# combo-02.net
KiCad netlist of a schematic drawn in EAGLE
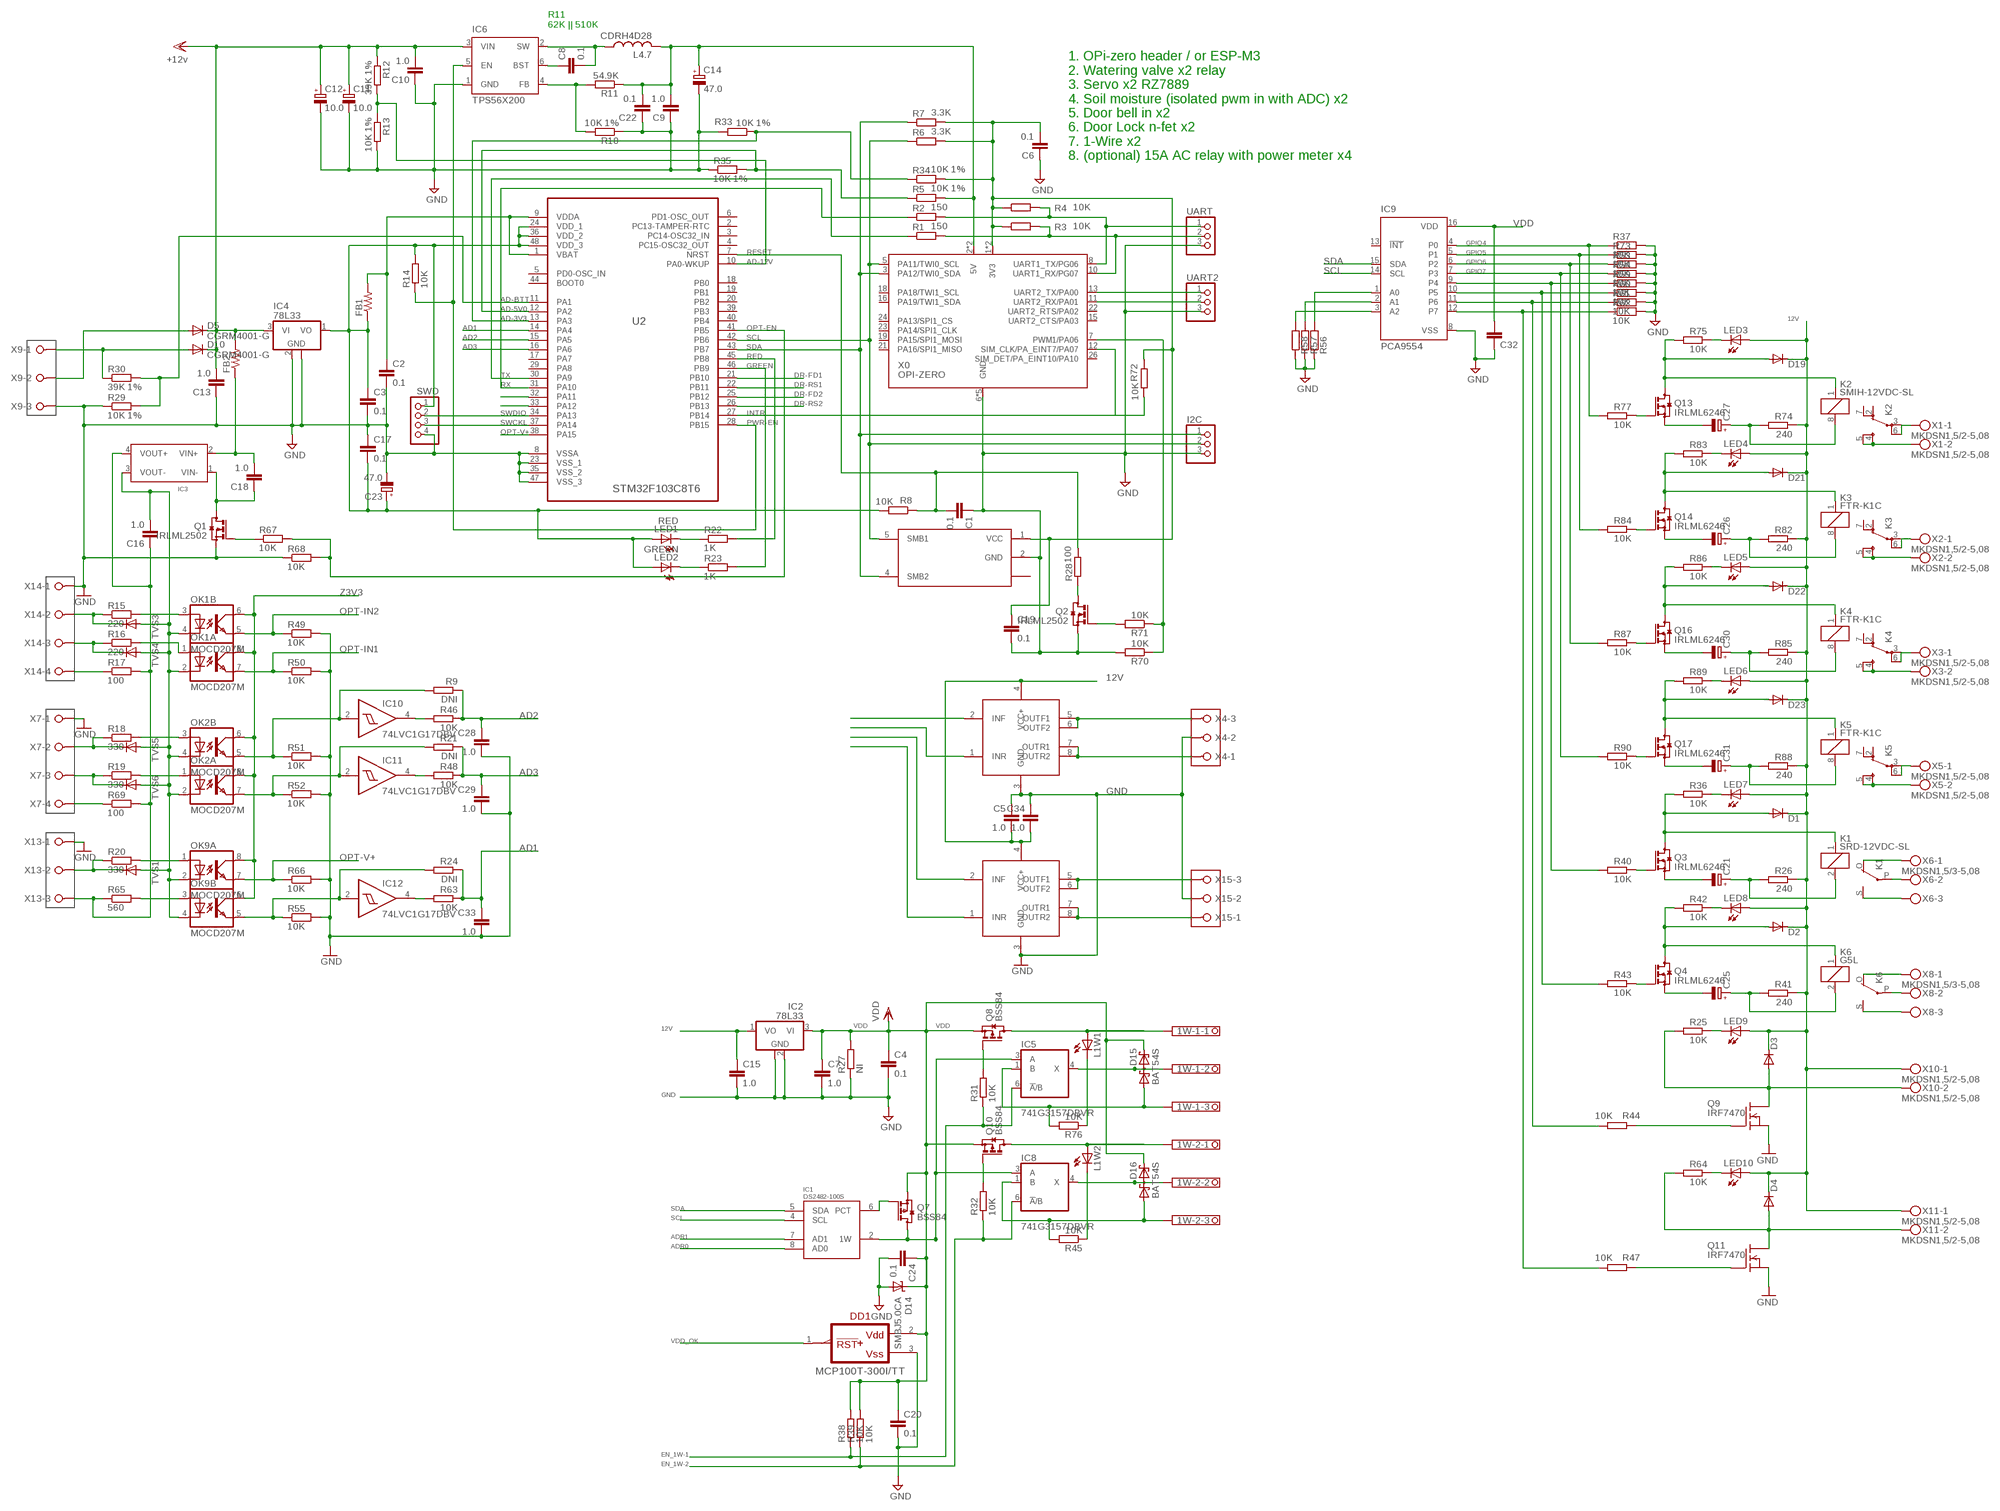
[diagram p0: schematic, sheet 1]

(export (version "E")
  (design (tool "Eeschema 10.0.6"))
  (components
    (comp (ref "1W-1")
      (value "1751251")
      (footprint "eagle-import:1751251")
      (libsource (lib "eagle-import") (part "1751251"))
    )
    (comp (ref "1W-2")
      (value "1751251")
      (footprint "eagle-import:1751251")
      (libsource (lib "eagle-import") (part "1751251"))
    )
    (comp (ref "C1")
      (value "0.1")
      (footprint "eagle-import:C0603")
      (libsource (lib "eagle-import") (part "C-EUC0603"))
    )
    (comp (ref "C2")
      (value "0.1")
      (footprint "eagle-import:C0603")
      (libsource (lib "eagle-import") (part "C-EUC0603"))
    )
    (comp (ref "C3")
      (value "0.1")
      (footprint "eagle-import:C0603")
      (libsource (lib "eagle-import") (part "C-EUC0603"))
    )
    (comp (ref "C4")
      (value "0.1")
      (footprint "eagle-import:C0603")
      (libsource (lib "eagle-import") (part "C-EUC0603"))
    )
    (comp (ref "C5")
      (value "1.0")
      (footprint "eagle-import:C0805")
      (libsource (lib "eagle-import") (part "C-EUC0805"))
    )
    (comp (ref "C6")
      (value "0.1")
      (footprint "eagle-import:C0805")
      (libsource (lib "eagle-import") (part "C-EUC0805"))
    )
    (comp (ref "C7")
      (value "1.0")
      (footprint "eagle-import:C0805")
      (libsource (lib "eagle-import") (part "C-EUC0805"))
    )
    (comp (ref "C8")
      (value "0.1")
      (footprint "eagle-import:C0805")
      (libsource (lib "eagle-import") (part "C-EUC0805"))
    )
    (comp (ref "C9")
      (value "1.0")
      (footprint "eagle-import:C0805")
      (libsource (lib "eagle-import") (part "C-EUC0805"))
    )
    (comp (ref "C10")
      (value "1.0")
      (footprint "eagle-import:C1206")
      (libsource (lib "eagle-import") (part "C-EUC1206"))
    )
    (comp (ref "C11")
      (value "10.0")
      (footprint "eagle-import:C_6032-28R")
      (libsource (lib "eagle-import") (part "CPOL-EUC/6032-28R"))
    )
    (comp (ref "C12")
      (value "10.0")
      (footprint "eagle-import:C_6032-28R")
      (libsource (lib "eagle-import") (part "CPOL-EUC/6032-28R"))
    )
    (comp (ref "C13")
      (value "1.0")
      (footprint "eagle-import:C1206")
      (libsource (lib "eagle-import") (part "C-EUC1206"))
    )
    (comp (ref "C14")
      (value "47.0")
      (footprint "eagle-import:B_3528-21R")
      (libsource (lib "eagle-import") (part "CPOL-EUB/3528-21R"))
    )
    (comp (ref "C15")
      (value "1.0")
      (footprint "eagle-import:C0805")
      (libsource (lib "eagle-import") (part "C-EUC0805"))
    )
    (comp (ref "C16")
      (value "1.0")
      (footprint "eagle-import:C1206")
      (libsource (lib "eagle-import") (part "C-EUC1206"))
    )
    (comp (ref "C17")
      (value "0.1")
      (footprint "eagle-import:C0603")
      (libsource (lib "eagle-import") (part "C-EUC0603"))
    )
    (comp (ref "C18")
      (value "1.0")
      (footprint "eagle-import:C1206")
      (libsource (lib "eagle-import") (part "C-EUC1206"))
    )
    (comp (ref "C19")
      (value "0.1")
      (footprint "eagle-import:C0603")
      (libsource (lib "eagle-import") (part "C-EUC0603"))
    )
    (comp (ref "C20")
      (value "0.1")
      (footprint "eagle-import:C0603")
      (libsource (lib "eagle-import") (part "C-EUC0603"))
    )
    (comp (ref "C21")
      (value "CPOL-EUE3.5-8")
      (footprint "eagle-import:E3,5-8")
      (libsource (lib "eagle-import") (part "CPOL-EUE3.5-8"))
    )
    (comp (ref "C22")
      (value "0.1")
      (footprint "eagle-import:C0805")
      (libsource (lib "eagle-import") (part "C-EUC0805"))
    )
    (comp (ref "C23")
      (value "47.0")
      (footprint "eagle-import:B_3528-21R")
      (libsource (lib "eagle-import") (part "CPOL-EUB/3528-21R"))
    )
    (comp (ref "C24")
      (value "0.1")
      (footprint "eagle-import:C0603")
      (libsource (lib "eagle-import") (part "C-EUC0603"))
    )
    (comp (ref "C25")
      (value "CPOL-EUE3.5-8")
      (footprint "eagle-import:E3,5-8")
      (libsource (lib "eagle-import") (part "CPOL-EUE3.5-8"))
    )
    (comp (ref "C26")
      (value "CPOL-EUE3.5-8")
      (footprint "eagle-import:E3,5-8")
      (libsource (lib "eagle-import") (part "CPOL-EUE3.5-8"))
    )
    (comp (ref "C27")
      (value "CPOL-EUE3.5-8")
      (footprint "eagle-import:E3,5-8")
      (libsource (lib "eagle-import") (part "CPOL-EUE3.5-8"))
    )
    (comp (ref "C28")
      (value "1.0")
      (footprint "eagle-import:C0805")
      (libsource (lib "eagle-import") (part "C-EUC0805"))
    )
    (comp (ref "C29")
      (value "1.0")
      (footprint "eagle-import:C0805")
      (libsource (lib "eagle-import") (part "C-EUC0805"))
    )
    (comp (ref "C30")
      (value "CPOL-EUE3.5-8")
      (footprint "eagle-import:E3,5-8")
      (libsource (lib "eagle-import") (part "CPOL-EUE3.5-8"))
    )
    (comp (ref "C31")
      (value "CPOL-EUE3.5-8")
      (footprint "eagle-import:E3,5-8")
      (libsource (lib "eagle-import") (part "CPOL-EUE3.5-8"))
    )
    (comp (ref "C32")
      (value "C-EUC0805")
      (footprint "eagle-import:C0805")
      (libsource (lib "eagle-import") (part "C-EUC0805"))
    )
    (comp (ref "C33")
      (value "1.0")
      (footprint "eagle-import:C0805")
      (libsource (lib "eagle-import") (part "C-EUC0805"))
    )
    (comp (ref "C34")
      (value "1.0")
      (footprint "eagle-import:C0805")
      (libsource (lib "eagle-import") (part "C-EUC0805"))
    )
    (comp (ref "D1")
      (value "DIODE-SOD123")
      (footprint "eagle-import:SOD123")
      (libsource (lib "eagle-import") (part "DIODE-SOD123"))
    )
    (comp (ref "D2")
      (value "DIODE-SOD123")
      (footprint "eagle-import:SOD123")
      (libsource (lib "eagle-import") (part "DIODE-SOD123"))
    )
    (comp (ref "D3")
      (value "DIODE-SOD123")
      (footprint "eagle-import:SOD123")
      (libsource (lib "eagle-import") (part "DIODE-SOD123"))
    )
    (comp (ref "D4")
      (value "DIODE-SOD123")
      (footprint "eagle-import:SOD123")
      (libsource (lib "eagle-import") (part "DIODE-SOD123"))
    )
    (comp (ref "D5")
      (value "CGRM4001-G")
      (footprint "eagle-import:SOD-123_MINI-SMA")
      (libsource (lib "eagle-import") (part "CGRM400-G1"))
    )
    (comp (ref "D10")
      (value "CGRM4001-G")
      (footprint "eagle-import:SOD-123_MINI-SMA")
      (libsource (lib "eagle-import") (part "CGRM400-G1"))
    )
    (comp (ref "D14")
      (value "SMBJ5.0CA")
      (footprint "eagle-import:SMBJ")
      (libsource (lib "eagle-import") (part "SUPPRESSOR-SMBJ"))
    )
    (comp (ref "D15")
      (value "BAT54S")
      (footprint "eagle-import:SOT23")
      (libsource (lib "eagle-import") (part "BAT54S"))
    )
    (comp (ref "D16")
      (value "BAT54S")
      (footprint "eagle-import:SOT23")
      (libsource (lib "eagle-import") (part "BAT54S"))
    )
    (comp (ref "D19")
      (value "DIODE-SOD123")
      (footprint "eagle-import:SOD123")
      (libsource (lib "eagle-import") (part "DIODE-SOD123"))
    )
    (comp (ref "D21")
      (value "DIODE-SOD123")
      (footprint "eagle-import:SOD123")
      (libsource (lib "eagle-import") (part "DIODE-SOD123"))
    )
    (comp (ref "D22")
      (value "DIODE-SOD123")
      (footprint "eagle-import:SOD123")
      (libsource (lib "eagle-import") (part "DIODE-SOD123"))
    )
    (comp (ref "D23")
      (value "DIODE-SOD123")
      (footprint "eagle-import:SOD123")
      (libsource (lib "eagle-import") (part "DIODE-SOD123"))
    )
    (comp (ref "DD1")
      (value "MCP100T-300I/TT")
      (footprint "eagle-import:SOT23")
      (libsource (lib "eagle-import") (part "MCP100T-300I/TT"))
    )
    (comp (ref "FB1")
      (value "R-US_R0805")
      (footprint "eagle-import:R0805")
      (libsource (lib "eagle-import") (part "R-US_R0805"))
    )
    (comp (ref "FB2")
      (value "R-US_R1206")
      (footprint "eagle-import:R1206")
      (libsource (lib "eagle-import") (part "R-US_R1206"))
    )
    (comp (ref "I2C")
      (value "PINHD-1X3")
      (footprint "eagle-import:1X03")
      (libsource (lib "eagle-import") (part "PINHD-1X3"))
    )
    (comp (ref "IC1")
      (value "DS2482-100S")
      (footprint "eagle-import:SO08")
      (libsource (lib "eagle-import") (part "DS2482-100S"))
    )
    (comp (ref "IC2")
      (value "78L33")
      (footprint "eagle-import:SOT89")
      (libsource (lib "eagle-import") (part "78LF05"))
    )
    (comp (ref "IC3")
      (value "DC-DC-CONV-4PIN-ISOLATINGMURATA-NME-05-12-SERIES")
      (footprint "eagle-import:DC-DC-MURATA-NME-05-12-SERIES")
      (libsource (lib "eagle-import") (part "DC-DC-CONV-4PIN-ISOLATINGMURATA-NME-05-12-SERIES"))
    )
    (comp (ref "IC4")
      (value "78L33")
      (footprint "eagle-import:SOT89")
      (libsource (lib "eagle-import") (part "78LF05"))
    )
    (comp (ref "IC5")
      (value "741G3157DBVR")
      (footprint "eagle-import:DBV_R-PDSO-G6")
      (libsource (lib "eagle-import") (part "741G3157DBVR"))
    )
    (comp (ref "IC6")
      (value "TPS56X200")
      (footprint "eagle-import:TSOT23-6_DDC")
      (libsource (lib "eagle-import") (part "TPS56X200"))
    )
    (comp (ref "IC7")
      (value "LTC1694")
      (footprint "eagle-import:SOT23-5")
      (libsource (lib "eagle-import") (part "LTC1694"))
    )
    (comp (ref "IC8")
      (value "741G3157DBVR")
      (footprint "eagle-import:DBV_R-PDSO-G6")
      (libsource (lib "eagle-import") (part "741G3157DBVR"))
    )
    (comp (ref "IC9")
      (value "PCA9554")
      (footprint "eagle-import:SO16W")
      (fields (field (name "MPN") "PCF8574T/3,512"))
      (libsource (lib "eagle-import") (part "PCF8574T"))
    )
    (comp (ref "IC10")
      (value "74LVC1G17DBV")
      (footprint "eagle-import:SOT23-5")
      (libsource (lib "eagle-import") (part "741G17DBVLVC"))
    )
    (comp (ref "IC11")
      (value "74LVC1G17DBV")
      (footprint "eagle-import:SOT23-5")
      (libsource (lib "eagle-import") (part "741G17DBVLVC"))
    )
    (comp (ref "IC12")
      (value "74LVC1G17DBV")
      (footprint "eagle-import:SOT23-5")
      (libsource (lib "eagle-import") (part "741G17DBVLVC"))
    )
    (comp (ref "K1")
      (value "SRD-12VDC-SL")
      (footprint "eagle-import:G5LE")
      (libsource (lib "eagle-import") (part "G5L"))
    )
    (comp (ref "K2")
      (value "SMIH-12VDC-SL")
      (footprint "eagle-import:FTR-K1C")
      (libsource (lib "eagle-import") (part "FTR-K1C"))
    )
    (comp (ref "K3")
      (value "FTR-K1C")
      (footprint "eagle-import:FTR-K1C")
      (libsource (lib "eagle-import") (part "FTR-K1C"))
    )
    (comp (ref "K4")
      (value "FTR-K1C")
      (footprint "eagle-import:FTR-K1C")
      (libsource (lib "eagle-import") (part "FTR-K1C"))
    )
    (comp (ref "K5")
      (value "FTR-K1C")
      (footprint "eagle-import:FTR-K1C")
      (libsource (lib "eagle-import") (part "FTR-K1C"))
    )
    (comp (ref "K6")
      (value "G5L")
      (footprint "eagle-import:G5LE")
      (libsource (lib "eagle-import") (part "G5L"))
    )
    (comp (ref "L1W1")
      (value "LEDSMT1206")
      (footprint "eagle-import:1206")
      (libsource (lib "eagle-import") (part "LEDSMT1206"))
    )
    (comp (ref "L1W2")
      (value "LEDSMT1206")
      (footprint "eagle-import:1206")
      (libsource (lib "eagle-import") (part "LEDSMT1206"))
    )
    (comp (ref "L4.7")
      (value "CDRH4D28")
      (footprint "eagle-import:CDRH4D28")
      (libsource (lib "eagle-import") (part "CDRH4D28"))
    )
    (comp (ref "LED1")
      (value "RED")
      (footprint "eagle-import:CHIPLED_1206")
      (libsource (lib "eagle-import") (part "LEDCHIPLED_1206"))
    )
    (comp (ref "LED2")
      (value "GREEN")
      (footprint "eagle-import:CHIPLED_1206")
      (libsource (lib "eagle-import") (part "LEDCHIPLED_1206"))
    )
    (comp (ref "LED3")
      (value "LEDSMT1206")
      (footprint "eagle-import:1206")
      (libsource (lib "eagle-import") (part "LEDSMT1206"))
    )
    (comp (ref "LED4")
      (value "LEDSMT1206")
      (footprint "eagle-import:1206")
      (libsource (lib "eagle-import") (part "LEDSMT1206"))
    )
    (comp (ref "LED5")
      (value "LEDSMT1206")
      (footprint "eagle-import:1206")
      (libsource (lib "eagle-import") (part "LEDSMT1206"))
    )
    (comp (ref "LED6")
      (value "LEDSMT1206")
      (footprint "eagle-import:1206")
      (libsource (lib "eagle-import") (part "LEDSMT1206"))
    )
    (comp (ref "LED7")
      (value "LEDSMT1206")
      (footprint "eagle-import:1206")
      (libsource (lib "eagle-import") (part "LEDSMT1206"))
    )
    (comp (ref "LED8")
      (value "LEDSMT1206")
      (footprint "eagle-import:1206")
      (libsource (lib "eagle-import") (part "LEDSMT1206"))
    )
    (comp (ref "LED9")
      (value "LEDSMT1206")
      (footprint "eagle-import:1206")
      (libsource (lib "eagle-import") (part "LEDSMT1206"))
    )
    (comp (ref "LED10")
      (value "LEDSMT1206")
      (footprint "eagle-import:1206")
      (libsource (lib "eagle-import") (part "LEDSMT1206"))
    )
    (comp (ref "OK1")
      (value "MOCD207M")
      (footprint "eagle-import:SOIC08-FAIRCHILD")
      (fields (field (name "MF") "FAIRCHILD SEMICONDUCTOR") (field (name "MPN") "MOCD207-M"))
      (libsource (lib "eagle-import") (part "MOCD20M7"))
    )
    (comp (ref "OK2")
      (value "MOCD207M")
      (footprint "eagle-import:SOIC08-FAIRCHILD")
      (fields (field (name "MF") "FAIRCHILD SEMICONDUCTOR") (field (name "MPN") "MOCD207-M"))
      (libsource (lib "eagle-import") (part "MOCD20M7"))
    )
    (comp (ref "OK9")
      (value "MOCD207M")
      (footprint "eagle-import:SOIC08-FAIRCHILD")
      (fields (field (name "MF") "FAIRCHILD SEMICONDUCTOR") (field (name "MPN") "MOCD207-M"))
      (libsource (lib "eagle-import") (part "MOCD20M7"))
    )
    (comp (ref "Q1")
      (value "IRLML2502")
      (footprint "eagle-import:SOT23")
      (libsource (lib "eagle-import") (part "IRLML2502"))
    )
    (comp (ref "Q2")
      (value "IRLML2502")
      (footprint "eagle-import:SOT23")
      (libsource (lib "eagle-import") (part "IRLML2502"))
    )
    (comp (ref "Q3")
      (value "IRLML6246")
      (footprint "eagle-import:SOT23")
      (libsource (lib "eagle-import") (part "BSS123"))
    )
    (comp (ref "Q4")
      (value "IRLML6246")
      (footprint "eagle-import:SOT23")
      (libsource (lib "eagle-import") (part "BSS123"))
    )
    (comp (ref "Q7")
      (value "BSS84")
      (footprint "eagle-import:SOT23")
      (libsource (lib "eagle-import") (part "BSS84"))
    )
    (comp (ref "Q8")
      (value "BSS84")
      (footprint "eagle-import:SOT23")
      (libsource (lib "eagle-import") (part "BSS84"))
    )
    (comp (ref "Q9")
      (value "IRF7470")
      (footprint "eagle-import:SO-8")
      (libsource (lib "eagle-import") (part "FDS5680"))
    )
    (comp (ref "Q10")
      (value "BSS84")
      (footprint "eagle-import:SOT23")
      (libsource (lib "eagle-import") (part "BSS84"))
    )
    (comp (ref "Q11")
      (value "IRF7470")
      (footprint "eagle-import:SO-8")
      (libsource (lib "eagle-import") (part "FDS5680"))
    )
    (comp (ref "Q13")
      (value "IRLML6246")
      (footprint "eagle-import:SOT23")
      (libsource (lib "eagle-import") (part "BSS123"))
    )
    (comp (ref "Q14")
      (value "IRLML6246")
      (footprint "eagle-import:SOT23")
      (libsource (lib "eagle-import") (part "BSS123"))
    )
    (comp (ref "Q16")
      (value "IRLML6246")
      (footprint "eagle-import:SOT23")
      (libsource (lib "eagle-import") (part "BSS123"))
    )
    (comp (ref "Q17")
      (value "IRLML6246")
      (footprint "eagle-import:SOT23")
      (libsource (lib "eagle-import") (part "BSS123"))
    )
    (comp (ref "R1")
      (value "150")
      (footprint "eagle-import:R0603")
      (libsource (lib "eagle-import") (part "R-EU_R0603"))
    )
    (comp (ref "R2")
      (value "150")
      (footprint "eagle-import:R0603")
      (libsource (lib "eagle-import") (part "R-EU_R0603"))
    )
    (comp (ref "R3")
      (value "10K")
      (footprint "eagle-import:R0603")
      (libsource (lib "eagle-import") (part "R-EU_R0603"))
    )
    (comp (ref "R4")
      (value "10K")
      (footprint "eagle-import:R0603")
      (libsource (lib "eagle-import") (part "R-EU_R0603"))
    )
    (comp (ref "R5")
      (value "10K 1%")
      (footprint "eagle-import:R0603")
      (libsource (lib "eagle-import") (part "R-EU_R0603"))
    )
    (comp (ref "R6")
      (value "3.3K")
      (footprint "eagle-import:R0603")
      (libsource (lib "eagle-import") (part "R-EU_R0603"))
    )
    (comp (ref "R7")
      (value "3.3K")
      (footprint "eagle-import:R0603")
      (libsource (lib "eagle-import") (part "R-EU_R0603"))
    )
    (comp (ref "R8")
      (value "10K")
      (footprint "eagle-import:R0603")
      (libsource (lib "eagle-import") (part "R-EU_R0603"))
    )
    (comp (ref "R9")
      (value "DNI")
      (footprint "eagle-import:R0603")
      (libsource (lib "eagle-import") (part "R-EU_R0603"))
    )
    (comp (ref "R10")
      (value "10K 1%")
      (footprint "eagle-import:R0603")
      (libsource (lib "eagle-import") (part "R-EU_R0603"))
    )
    (comp (ref "R11")
      (value "54.9K")
      (footprint "eagle-import:R0603")
      (libsource (lib "eagle-import") (part "R-EU_R0603"))
    )
    (comp (ref "R12")
      (value "39K 1%")
      (footprint "eagle-import:R0603")
      (libsource (lib "eagle-import") (part "R-EU_R0603"))
    )
    (comp (ref "R13")
      (value "10K 1%")
      (footprint "eagle-import:R0603")
      (libsource (lib "eagle-import") (part "R-EU_R0603"))
    )
    (comp (ref "R14")
      (value "10K")
      (footprint "eagle-import:R0603")
      (libsource (lib "eagle-import") (part "R-EU_R0603"))
    )
    (comp (ref "R15")
      (value "220")
      (footprint "eagle-import:R0603")
      (libsource (lib "eagle-import") (part "R-EU_R0603"))
    )
    (comp (ref "R16")
      (value "220")
      (footprint "eagle-import:R0603")
      (libsource (lib "eagle-import") (part "R-EU_R0603"))
    )
    (comp (ref "R17")
      (value "100")
      (footprint "eagle-import:R0603")
      (libsource (lib "eagle-import") (part "R-EU_R0603"))
    )
    (comp (ref "R18")
      (value "330")
      (footprint "eagle-import:R0603")
      (libsource (lib "eagle-import") (part "R-EU_R0603"))
    )
    (comp (ref "R19")
      (value "330")
      (footprint "eagle-import:R0603")
      (libsource (lib "eagle-import") (part "R-EU_R0603"))
    )
    (comp (ref "R20")
      (value "330")
      (footprint "eagle-import:R0603")
      (libsource (lib "eagle-import") (part "R-EU_R0603"))
    )
    (comp (ref "R21")
      (value "DNI")
      (footprint "eagle-import:R0603")
      (libsource (lib "eagle-import") (part "R-EU_R0603"))
    )
    (comp (ref "R22")
      (value "1K")
      (footprint "eagle-import:R0603")
      (libsource (lib "eagle-import") (part "R-EU_R0603"))
    )
    (comp (ref "R23")
      (value "1K")
      (footprint "eagle-import:R0603")
      (libsource (lib "eagle-import") (part "R-EU_R0603"))
    )
    (comp (ref "R24")
      (value "DNI")
      (footprint "eagle-import:R0603")
      (libsource (lib "eagle-import") (part "R-EU_R0603"))
    )
    (comp (ref "R25")
      (value "10K")
      (footprint "eagle-import:R0603")
      (libsource (lib "eagle-import") (part "R-EU_R0603"))
    )
    (comp (ref "R26")
      (value "240")
      (footprint "eagle-import:R1206")
      (libsource (lib "eagle-import") (part "R-EU_R1206"))
    )
    (comp (ref "R27")
      (value "NI")
      (footprint "eagle-import:R0603")
      (libsource (lib "eagle-import") (part "R-EU_R0603"))
    )
    (comp (ref "R28")
      (value "100")
      (footprint "eagle-import:R0603")
      (libsource (lib "eagle-import") (part "R-EU_R0603"))
    )
    (comp (ref "R29")
      (value "10K 1%")
      (footprint "eagle-import:R0603")
      (libsource (lib "eagle-import") (part "R-EU_R0603"))
    )
    (comp (ref "R30")
      (value "39K 1%")
      (footprint "eagle-import:R0603")
      (libsource (lib "eagle-import") (part "R-EU_R0603"))
    )
    (comp (ref "R31")
      (value "10K")
      (footprint "eagle-import:R0603")
      (libsource (lib "eagle-import") (part "R-EU_R0603"))
    )
    (comp (ref "R32")
      (value "10K")
      (footprint "eagle-import:R0603")
      (libsource (lib "eagle-import") (part "R-EU_R0603"))
    )
    (comp (ref "R33")
      (value "10K 1%")
      (footprint "eagle-import:R0603")
      (libsource (lib "eagle-import") (part "R-EU_R0603"))
    )
    (comp (ref "R34")
      (value "10K 1%")
      (footprint "eagle-import:R0603")
      (libsource (lib "eagle-import") (part "R-EU_R0603"))
    )
    (comp (ref "R35")
      (value "10K 1%")
      (footprint "eagle-import:R0603")
      (libsource (lib "eagle-import") (part "R-EU_R0603"))
    )
    (comp (ref "R36")
      (value "10K")
      (footprint "eagle-import:R0603")
      (libsource (lib "eagle-import") (part "R-EU_R0603"))
    )
    (comp (ref "R37")
      (value "10K")
      (footprint "eagle-import:R0603")
      (libsource (lib "eagle-import") (part "R-EU_R0603"))
    )
    (comp (ref "R38")
      (value "10K")
      (footprint "eagle-import:R0603")
      (libsource (lib "eagle-import") (part "R-EU_R0603"))
    )
    (comp (ref "R39")
      (value "10K")
      (footprint "eagle-import:R0603")
      (libsource (lib "eagle-import") (part "R-EU_R0603"))
    )
    (comp (ref "R40")
      (value "10K")
      (footprint "eagle-import:R0603")
      (libsource (lib "eagle-import") (part "R-EU_R0603"))
    )
    (comp (ref "R41")
      (value "240")
      (footprint "eagle-import:R1206")
      (libsource (lib "eagle-import") (part "R-EU_R1206"))
    )
    (comp (ref "R42")
      (value "10K")
      (footprint "eagle-import:R0603")
      (libsource (lib "eagle-import") (part "R-EU_R0603"))
    )
    (comp (ref "R43")
      (value "10K")
      (footprint "eagle-import:R0603")
      (libsource (lib "eagle-import") (part "R-EU_R0603"))
    )
    (comp (ref "R44")
      (value "10K")
      (footprint "eagle-import:R0603")
      (libsource (lib "eagle-import") (part "R-EU_R0603"))
    )
    (comp (ref "R45")
      (value "10K")
      (footprint "eagle-import:R0603")
      (libsource (lib "eagle-import") (part "R-EU_R0603"))
    )
    (comp (ref "R46")
      (value "10K")
      (footprint "eagle-import:R0603")
      (libsource (lib "eagle-import") (part "R-EU_R0603"))
    )
    (comp (ref "R47")
      (value "10K")
      (footprint "eagle-import:R0603")
      (libsource (lib "eagle-import") (part "R-EU_R0603"))
    )
    (comp (ref "R48")
      (value "10K")
      (footprint "eagle-import:R0603")
      (libsource (lib "eagle-import") (part "R-EU_R0603"))
    )
    (comp (ref "R49")
      (value "10K")
      (footprint "eagle-import:R0603")
      (libsource (lib "eagle-import") (part "R-EU_R0603"))
    )
    (comp (ref "R50")
      (value "10K")
      (footprint "eagle-import:R0603")
      (libsource (lib "eagle-import") (part "R-EU_R0603"))
    )
    (comp (ref "R51")
      (value "10K")
      (footprint "eagle-import:R0603")
      (libsource (lib "eagle-import") (part "R-EU_R0603"))
    )
    (comp (ref "R52")
      (value "10K")
      (footprint "eagle-import:R0603")
      (libsource (lib "eagle-import") (part "R-EU_R0603"))
    )
    (comp (ref "R53")
      (value "10K")
      (footprint "eagle-import:R0603")
      (libsource (lib "eagle-import") (part "R-EU_R0603"))
    )
    (comp (ref "R54")
      (value "10K")
      (footprint "eagle-import:R0603")
      (libsource (lib "eagle-import") (part "R-EU_R0603"))
    )
    (comp (ref "R55")
      (value "10K")
      (footprint "eagle-import:R0603")
      (libsource (lib "eagle-import") (part "R-EU_R0603"))
    )
    (comp (ref "R56")
      (value "R-EU_R0603")
      (footprint "eagle-import:R0603")
      (libsource (lib "eagle-import") (part "R-EU_R0603"))
    )
    (comp (ref "R57")
      (value "R-EU_R0603")
      (footprint "eagle-import:R0603")
      (libsource (lib "eagle-import") (part "R-EU_R0603"))
    )
    (comp (ref "R58")
      (value "R-EU_R0603")
      (footprint "eagle-import:R0603")
      (libsource (lib "eagle-import") (part "R-EU_R0603"))
    )
    (comp (ref "R59")
      (value "10K")
      (footprint "eagle-import:R0603")
      (libsource (lib "eagle-import") (part "R-EU_R0603"))
    )
    (comp (ref "R60")
      (value "10K")
      (footprint "eagle-import:R0603")
      (libsource (lib "eagle-import") (part "R-EU_R0603"))
    )
    (comp (ref "R61")
      (value "10K")
      (footprint "eagle-import:R0603")
      (libsource (lib "eagle-import") (part "R-EU_R0603"))
    )
    (comp (ref "R62")
      (value "10K")
      (footprint "eagle-import:R0603")
      (libsource (lib "eagle-import") (part "R-EU_R0603"))
    )
    (comp (ref "R63")
      (value "10K")
      (footprint "eagle-import:R0603")
      (libsource (lib "eagle-import") (part "R-EU_R0603"))
    )
    (comp (ref "R64")
      (value "10K")
      (footprint "eagle-import:R0603")
      (libsource (lib "eagle-import") (part "R-EU_R0603"))
    )
    (comp (ref "R65")
      (value "560")
      (footprint "eagle-import:R0603")
      (libsource (lib "eagle-import") (part "R-EU_R0603"))
    )
    (comp (ref "R66")
      (value "10K")
      (footprint "eagle-import:R0603")
      (libsource (lib "eagle-import") (part "R-EU_R0603"))
    )
    (comp (ref "R67")
      (value "10K")
      (footprint "eagle-import:R0603")
      (libsource (lib "eagle-import") (part "R-EU_R0603"))
    )
    (comp (ref "R68")
      (value "10K")
      (footprint "eagle-import:R0603")
      (libsource (lib "eagle-import") (part "R-EU_R0603"))
    )
    (comp (ref "R69")
      (value "100")
      (footprint "eagle-import:R0603")
      (libsource (lib "eagle-import") (part "R-EU_R0603"))
    )
    (comp (ref "R70")
      (value "10K")
      (footprint "eagle-import:R0603")
      (libsource (lib "eagle-import") (part "R-EU_R0603"))
    )
    (comp (ref "R71")
      (value "10K")
      (footprint "eagle-import:R0603")
      (libsource (lib "eagle-import") (part "R-EU_R0603"))
    )
    (comp (ref "R72")
      (value "10K")
      (footprint "eagle-import:R0603")
      (libsource (lib "eagle-import") (part "R-EU_R0603"))
    )
    (comp (ref "R73")
      (value "10K")
      (footprint "eagle-import:R0603")
      (libsource (lib "eagle-import") (part "R-EU_R0603"))
    )
    (comp (ref "R74")
      (value "240")
      (footprint "eagle-import:R1206")
      (libsource (lib "eagle-import") (part "R-EU_R1206"))
    )
    (comp (ref "R75")
      (value "10K")
      (footprint "eagle-import:R0603")
      (libsource (lib "eagle-import") (part "R-EU_R0603"))
    )
    (comp (ref "R76")
      (value "10K")
      (footprint "eagle-import:R0603")
      (libsource (lib "eagle-import") (part "R-EU_R0603"))
    )
    (comp (ref "R77")
      (value "10K")
      (footprint "eagle-import:R0603")
      (libsource (lib "eagle-import") (part "R-EU_R0603"))
    )
    (comp (ref "R82")
      (value "240")
      (footprint "eagle-import:R1206")
      (libsource (lib "eagle-import") (part "R-EU_R1206"))
    )
    (comp (ref "R83")
      (value "10K")
      (footprint "eagle-import:R0603")
      (libsource (lib "eagle-import") (part "R-EU_R0603"))
    )
    (comp (ref "R84")
      (value "10K")
      (footprint "eagle-import:R0603")
      (libsource (lib "eagle-import") (part "R-EU_R0603"))
    )
    (comp (ref "R85")
      (value "240")
      (footprint "eagle-import:R1206")
      (libsource (lib "eagle-import") (part "R-EU_R1206"))
    )
    (comp (ref "R86")
      (value "10K")
      (footprint "eagle-import:R0603")
      (libsource (lib "eagle-import") (part "R-EU_R0603"))
    )
    (comp (ref "R87")
      (value "10K")
      (footprint "eagle-import:R0603")
      (libsource (lib "eagle-import") (part "R-EU_R0603"))
    )
    (comp (ref "R88")
      (value "240")
      (footprint "eagle-import:R1206")
      (libsource (lib "eagle-import") (part "R-EU_R1206"))
    )
    (comp (ref "R89")
      (value "10K")
      (footprint "eagle-import:R0603")
      (libsource (lib "eagle-import") (part "R-EU_R0603"))
    )
    (comp (ref "R90")
      (value "10K")
      (footprint "eagle-import:R0603")
      (libsource (lib "eagle-import") (part "R-EU_R0603"))
    )
    (comp (ref "SWD")
      (value "PINHD-1X4")
      (footprint "eagle-import:1X04")
      (libsource (lib "eagle-import") (part "PINHD-1X4"))
    )
    (comp (ref "TVS1")
      (value "DIODE-SOD323-W")
      (footprint "eagle-import:SOD323-W")
      (libsource (lib "eagle-import") (part "DIODE-SOD323-W"))
    )
    (comp (ref "TVS3")
      (value "DIODE-SOD323-W")
      (footprint "eagle-import:SOD323-W")
      (libsource (lib "eagle-import") (part "DIODE-SOD323-W"))
    )
    (comp (ref "TVS4")
      (value "DIODE-SOD323-W")
      (footprint "eagle-import:SOD323-W")
      (libsource (lib "eagle-import") (part "DIODE-SOD323-W"))
    )
    (comp (ref "TVS5")
      (value "DIODE-SOD323-W")
      (footprint "eagle-import:SOD323-W")
      (libsource (lib "eagle-import") (part "DIODE-SOD323-W"))
    )
    (comp (ref "TVS6")
      (value "DIODE-SOD323-W")
      (footprint "eagle-import:SOD323-W")
      (libsource (lib "eagle-import") (part "DIODE-SOD323-W"))
    )
    (comp (ref "U$10")
      (value "RZ7889")
      (footprint "eagle-import:SO8")
      (libsource (lib "eagle-import") (part "RZ7889"))
    )
    (comp (ref "U$11")
      (value "RZ7889")
      (footprint "eagle-import:SO8")
      (libsource (lib "eagle-import") (part "RZ7889"))
    )
    (comp (ref "U2")
      (value "STM32F103C8T6")
      (footprint "eagle-import:QFP50P900X900X160-48N")
      (fields (field (name "MPN") "STM32F100CBT6B"))
      (libsource (lib "eagle-import") (part "STM32F100CBT6B"))
    )
    (comp (ref "UART")
      (value "PINHD-1X3")
      (footprint "eagle-import:1X03")
      (libsource (lib "eagle-import") (part "PINHD-1X3"))
    )
    (comp (ref "UART2")
      (value "PINHD-1X3")
      (footprint "eagle-import:1X03")
      (libsource (lib "eagle-import") (part "PINHD-1X3"))
    )
    (comp (ref "X0")
      (value "OPI-ZERO")
      (footprint "eagle-import:OPI0")
      (libsource (lib "eagle-import") (part "OPI-ZERO"))
    )
    (comp (ref "X1")
      (value "MKDSN1,5/2-5,08")
      (footprint "eagle-import:MKDSN1,5_2-5,08")
      (libsource (lib "eagle-import") (part "MKDSN1,5/2-5,08"))
    )
    (comp (ref "X2")
      (value "MKDSN1,5/2-5,08")
      (footprint "eagle-import:MKDSN1,5_2-5,08")
      (libsource (lib "eagle-import") (part "MKDSN1,5/2-5,08"))
    )
    (comp (ref "X3")
      (value "MKDSN1,5/2-5,08")
      (footprint "eagle-import:MKDSN1,5_2-5,08")
      (libsource (lib "eagle-import") (part "MKDSN1,5/2-5,08"))
    )
    (comp (ref "X4")
      (value "W237-03P")
      (footprint "eagle-import:W237-133")
      (libsource (lib "eagle-import") (part "W237-03P"))
    )
    (comp (ref "X5")
      (value "MKDSN1,5/2-5,08")
      (footprint "eagle-import:MKDSN1,5_2-5,08")
      (libsource (lib "eagle-import") (part "MKDSN1,5/2-5,08"))
    )
    (comp (ref "X6")
      (value "MKDSN1,5/3-5,08")
      (footprint "eagle-import:MKDSN1,5_3-5,08")
      (libsource (lib "eagle-import") (part "MKDSN1,5/3-5,08"))
    )
    (comp (ref "X7")
      (value "W237-04P")
      (footprint "eagle-import:W237-4P")
      (libsource (lib "eagle-import") (part "W237-04P"))
    )
    (comp (ref "X8")
      (value "MKDSN1,5/3-5,08")
      (footprint "eagle-import:MKDSN1,5_3-5,08")
      (libsource (lib "eagle-import") (part "MKDSN1,5/3-5,08"))
    )
    (comp (ref "X9")
      (value "W237-03P")
      (footprint "eagle-import:W237-133")
      (libsource (lib "eagle-import") (part "W237-03P"))
    )
    (comp (ref "X10")
      (value "MKDSN1,5/2-5,08")
      (footprint "eagle-import:MKDSN1,5_2-5,08")
      (libsource (lib "eagle-import") (part "MKDSN1,5/2-5,08"))
    )
    (comp (ref "X11")
      (value "MKDSN1,5/2-5,08")
      (footprint "eagle-import:MKDSN1,5_2-5,08")
      (libsource (lib "eagle-import") (part "MKDSN1,5/2-5,08"))
    )
    (comp (ref "X13")
      (value "W237-03P")
      (footprint "eagle-import:W237-133")
      (libsource (lib "eagle-import") (part "W237-03P"))
    )
    (comp (ref "X14")
      (value "W237-04P")
      (footprint "eagle-import:W237-4P")
      (libsource (lib "eagle-import") (part "W237-04P"))
    )
    (comp (ref "X15")
      (value "W237-03P")
      (footprint "eagle-import:W237-133")
      (libsource (lib "eagle-import") (part "W237-03P"))
    )
  )
  (nets
    (net (code "1") (name "+12v") (class "Default")
      (node (ref "C10") (pin "2") (pinfunction "2_2") (pintype "passive"))
      (node (ref "C11") (pin "+") (pinfunction "+_+") (pintype "passive"))
      (node (ref "C12") (pin "+") (pinfunction "+_+") (pintype "passive"))
      (node (ref "C13") (pin "2") (pinfunction "2_2") (pintype "passive"))
      (node (ref "C15") (pin "1") (pinfunction "1_1") (pintype "passive"))
      (node (ref "C34") (pin "2") (pinfunction "2_2") (pintype "passive"))
      (node (ref "C5") (pin "2") (pinfunction "2_2") (pintype "passive"))
      (node (ref "D1") (pin "C") (pinfunction "C_C") (pintype "passive"))
      (node (ref "D10") (pin "C") (pinfunction "C_C") (pintype "passive"))
      (node (ref "D19") (pin "C") (pinfunction "C_C") (pintype "passive"))
      (node (ref "D2") (pin "C") (pinfunction "C_C") (pintype "passive"))
      (node (ref "D21") (pin "C") (pinfunction "C_C") (pintype "passive"))
      (node (ref "D22") (pin "C") (pinfunction "C_C") (pintype "passive"))
      (node (ref "D23") (pin "C") (pinfunction "C_C") (pintype "passive"))
      (node (ref "D3") (pin "C") (pinfunction "C_C") (pintype "passive"))
      (node (ref "D4") (pin "C") (pinfunction "C_C") (pintype "passive"))
      (node (ref "D5") (pin "C") (pinfunction "C_C") (pintype "passive"))
      (node (ref "FB2") (pin "2") (pinfunction "2_2") (pintype "passive"))
      (node (ref "IC2") (pin "1") (pinfunction "VO_1") (pintype "passive"))
      (node (ref "IC4") (pin "3") (pinfunction "VI_3") (pintype "input"))
      (node (ref "IC6") (pin "3") (pinfunction "VIN_3") (pintype "input"))
      (node (ref "LED10") (pin "A") (pinfunction "A_A") (pintype "passive"))
      (node (ref "LED3") (pin "A") (pinfunction "A_A") (pintype "passive"))
      (node (ref "LED4") (pin "A") (pinfunction "A_A") (pintype "passive"))
      (node (ref "LED5") (pin "A") (pinfunction "A_A") (pintype "passive"))
      (node (ref "LED6") (pin "A") (pinfunction "A_A") (pintype "passive"))
      (node (ref "LED7") (pin "A") (pinfunction "A_A") (pintype "passive"))
      (node (ref "LED8") (pin "A") (pinfunction "A_A") (pintype "passive"))
      (node (ref "LED9") (pin "A") (pinfunction "A_A") (pintype "passive"))
      (node (ref "R12") (pin "1") (pinfunction "1_1") (pintype "passive"))
      (node (ref "R26") (pin "1") (pinfunction "1_1") (pintype "passive"))
      (node (ref "R41") (pin "1") (pinfunction "1_1") (pintype "passive"))
      (node (ref "R74") (pin "1") (pinfunction "1_1") (pintype "passive"))
      (node (ref "R82") (pin "1") (pinfunction "1_1") (pintype "passive"))
      (node (ref "R85") (pin "1") (pinfunction "1_1") (pintype "passive"))
      (node (ref "R88") (pin "1") (pinfunction "1_1") (pintype "passive"))
      (node (ref "U$10") (pin "4") (pinfunction "VCC+_4") (pintype "bidirectional"))
      (node (ref "U$11") (pin "4") (pinfunction "VCC+_4") (pintype "bidirectional"))
      (node (ref "X10") (pin "1") (pinfunction "KL_1") (pintype "passive"))
      (node (ref "X11") (pin "1") (pinfunction "KL_1") (pintype "passive"))
    )
    (net (code "2") (name "/AD-3V3") (class "Default")
      (node (ref "R33") (pin "1") (pinfunction "1_1") (pintype "passive"))
      (node (ref "R34") (pin "1") (pinfunction "1_1") (pintype "passive"))
      (node (ref "U2") (pin "13") (pinfunction "PA3_13") (pintype "bidirectional"))
    )
    (net (code "3") (name "/AD-5V0") (class "Default")
      (node (ref "R35") (pin "2") (pinfunction "2_2") (pintype "passive"))
      (node (ref "R5") (pin "1") (pinfunction "1_1") (pintype "passive"))
      (node (ref "U2") (pin "12") (pinfunction "PA2_12") (pintype "bidirectional"))
    )
    (net (code "4") (name "/AD-12V") (class "Default")
      (node (ref "R12") (pin "2") (pinfunction "2_2") (pintype "passive"))
      (node (ref "R13") (pin "1") (pinfunction "1_1") (pintype "passive"))
      (node (ref "U2") (pin "10") (pinfunction "PA0-WKUP_10") (pintype "bidirectional"))
    )
    (net (code "5") (name "/AD-BTT") (class "Default")
      (node (ref "R29") (pin "2") (pinfunction "2_2") (pintype "passive"))
      (node (ref "R30") (pin "2") (pinfunction "2_2") (pintype "passive"))
      (node (ref "U2") (pin "11") (pinfunction "PA1_11") (pintype "bidirectional"))
    )
    (net (code "6") (name "/AD1") (class "Default")
      (node (ref "C33") (pin "1") (pinfunction "1_1") (pintype "passive"))
      (node (ref "R24") (pin "1") (pinfunction "1_1") (pintype "passive"))
      (node (ref "R63") (pin "1") (pinfunction "1_1") (pintype "passive"))
      (node (ref "U2") (pin "14") (pinfunction "PA4_14") (pintype "bidirectional"))
    )
    (net (code "7") (name "/AD2") (class "Default")
      (node (ref "C28") (pin "1") (pinfunction "1_1") (pintype "passive"))
      (node (ref "R46") (pin "1") (pinfunction "1_1") (pintype "passive"))
      (node (ref "R9") (pin "1") (pinfunction "1_1") (pintype "passive"))
      (node (ref "U2") (pin "15") (pinfunction "PA5_15") (pintype "bidirectional"))
    )
    (net (code "8") (name "/AD3") (class "Default")
      (node (ref "C29") (pin "1") (pinfunction "1_1") (pintype "passive"))
      (node (ref "R21") (pin "1") (pinfunction "1_1") (pintype "passive"))
      (node (ref "R48") (pin "1") (pinfunction "1_1") (pintype "passive"))
      (node (ref "U2") (pin "16") (pinfunction "PA6_16") (pintype "bidirectional"))
    )
    (net (code "9") (name "/ADR0") (class "Default")
      (node (ref "IC1") (pin "8") (pinfunction "AD0_8") (pintype "input"))
    )
    (net (code "10") (name "/ADR1") (class "Default")
      (node (ref "IC1") (pin "7") (pinfunction "AD1_7") (pintype "input"))
    )
    (net (code "11") (name "/DR-FD1") (class "Default")
      (node (ref "U2") (pin "21") (pinfunction "PB10_21") (pintype "bidirectional"))
    )
    (net (code "12") (name "/DR-FD2") (class "Default")
      (node (ref "U2") (pin "25") (pinfunction "PB12_25") (pintype "bidirectional"))
    )
    (net (code "13") (name "/DR-RS1") (class "Default")
      (node (ref "U2") (pin "22") (pinfunction "PB11_22") (pintype "bidirectional"))
    )
    (net (code "14") (name "/DR-RS2") (class "Default")
      (node (ref "U2") (pin "26") (pinfunction "PB13_26") (pintype "bidirectional"))
    )
    (net (code "15") (name "/EN_1W-1") (class "Default")
      (node (ref "IC5") (pin "6") (pinfunction "~{A}/B_6") (pintype "input"))
      (node (ref "R31") (pin "1") (pinfunction "1_1") (pintype "passive"))
      (node (ref "R38") (pin "1") (pinfunction "1_1") (pintype "passive"))
    )
    (net (code "16") (name "/EN_1W-2") (class "Default")
      (node (ref "IC8") (pin "6") (pinfunction "~{A}/B_6") (pintype "input"))
      (node (ref "R32") (pin "1") (pinfunction "1_1") (pintype "passive"))
      (node (ref "R39") (pin "1") (pinfunction "1_1") (pintype "passive"))
    )
    (net (code "17") (name "/GPIO4") (class "Default")
      (node (ref "IC9") (pin "4") (pinfunction "P0_4") (pintype "bidirectional"))
      (node (ref "R37") (pin "1") (pinfunction "1_1") (pintype "passive"))
      (node (ref "R77") (pin "2") (pinfunction "2_2") (pintype "passive"))
    )
    (net (code "18") (name "/GPIO5") (class "Default")
      (node (ref "IC9") (pin "5") (pinfunction "P1_5") (pintype "bidirectional"))
      (node (ref "R73") (pin "1") (pinfunction "1_1") (pintype "passive"))
      (node (ref "R84") (pin "2") (pinfunction "2_2") (pintype "passive"))
    )
    (net (code "19") (name "/GPIO6") (class "Default")
      (node (ref "IC9") (pin "6") (pinfunction "P2_6") (pintype "bidirectional"))
      (node (ref "R53") (pin "1") (pinfunction "1_1") (pintype "passive"))
      (node (ref "R87") (pin "2") (pinfunction "2_2") (pintype "passive"))
    )
    (net (code "20") (name "/GPIO7") (class "Default")
      (node (ref "IC9") (pin "7") (pinfunction "P3_7") (pintype "bidirectional"))
      (node (ref "R54") (pin "1") (pinfunction "1_1") (pintype "passive"))
      (node (ref "R90") (pin "2") (pinfunction "2_2") (pintype "passive"))
    )
    (net (code "21") (name "/GREEN") (class "Default")
      (node (ref "R23") (pin "2") (pinfunction "2_2") (pintype "passive"))
      (node (ref "U2") (pin "46") (pinfunction "PB9_46") (pintype "bidirectional"))
    )
    (net (code "22") (name "/INTR") (class "Default")
      (node (ref "R72") (pin "2") (pinfunction "2_2") (pintype "passive"))
      (node (ref "U2") (pin "27") (pinfunction "PB14_27") (pintype "bidirectional"))
      (node (ref "X0") (pin "12") (pinfunction "SIM_CLK/PA_EINT7/PA07_12") (pintype "bidirectional"))
    )
    (net (code "23") (name "/OPT-EN") (class "Default")
      (node (ref "R67") (pin "2") (pinfunction "2_2") (pintype "passive"))
      (node (ref "R68") (pin "2") (pinfunction "2_2") (pintype "passive"))
      (node (ref "U2") (pin "41") (pinfunction "PB5_41") (pintype "bidirectional"))
    )
    (net (code "24") (name "/OPT-IN1") (class "Default")
      (node (ref "OK1") (pin "7") (pinfunction "EMIT_7") (pintype "passive"))
      (node (ref "R50") (pin "1") (pinfunction "1_1") (pintype "passive"))
      (node (ref "U2") (pin "32") (pinfunction "PA11_32") (pintype "bidirectional"))
    )
    (net (code "25") (name "/OPT-IN2") (class "Default")
      (node (ref "OK1") (pin "5") (pinfunction "EMIT_5") (pintype "passive"))
      (node (ref "R49") (pin "1") (pinfunction "1_1") (pintype "passive"))
      (node (ref "U2") (pin "33") (pinfunction "PA12_33") (pintype "bidirectional"))
    )
    (net (code "26") (name "/OPT-V+") (class "Default")
      (node (ref "OK9") (pin "7") (pinfunction "EMIT_7") (pintype "passive"))
      (node (ref "R66") (pin "1") (pinfunction "1_1") (pintype "passive"))
      (node (ref "U2") (pin "38") (pinfunction "PA15_38") (pintype "bidirectional"))
    )
    (net (code "27") (name "/PWR-EN") (class "Default")
      (node (ref "IC6") (pin "5") (pinfunction "EN_5") (pintype "input"))
      (node (ref "R14") (pin "1") (pinfunction "1_1") (pintype "passive"))
      (node (ref "U2") (pin "28") (pinfunction "PB15_28") (pintype "bidirectional"))
    )
    (net (code "28") (name "/RED") (class "Default")
      (node (ref "R22") (pin "2") (pinfunction "2_2") (pintype "passive"))
      (node (ref "U2") (pin "45") (pinfunction "PB8_45") (pintype "bidirectional"))
    )
    (net (code "29") (name "/RESET") (class "Default")
      (node (ref "C1") (pin "2") (pinfunction "2_2") (pintype "passive"))
      (node (ref "R28") (pin "2") (pinfunction "2_2") (pintype "passive"))
      (node (ref "R8") (pin "1") (pinfunction "1_1") (pintype "passive"))
      (node (ref "U2") (pin "7") (pinfunction "NRST_7") (pintype "bidirectional"))
    )
    (net (code "30") (name "/RX") (class "Default")
      (node (ref "R2") (pin "1") (pinfunction "1_1") (pintype "passive"))
      (node (ref "U2") (pin "31") (pinfunction "PA10_31") (pintype "bidirectional"))
    )
    (net (code "31") (name "/SCL") (class "Default")
      (node (ref "I2C") (pin "2") (pinfunction "2_2") (pintype "passive"))
      (node (ref "IC1") (pin "4") (pinfunction "SCL_4") (pintype "input"))
      (node (ref "IC7") (pin "5") (pinfunction "SMB1_5") (pintype "bidirectional"))
      (node (ref "IC9") (pin "14") (pinfunction "SCL_14") (pintype "input"))
      (node (ref "R6") (pin "1") (pinfunction "1_1") (pintype "passive"))
      (node (ref "U2") (pin "42") (pinfunction "PB6_42") (pintype "bidirectional"))
      (node (ref "X0") (pin "5") (pinfunction "PA11/TWI0_SCL_5") (pintype "bidirectional"))
    )
    (net (code "32") (name "/SDA") (class "Default")
      (node (ref "I2C") (pin "1") (pinfunction "1_1") (pintype "passive"))
      (node (ref "IC1") (pin "5") (pinfunction "SDA_5") (pintype "bidirectional"))
      (node (ref "IC7") (pin "4") (pinfunction "SMB2_4") (pintype "bidirectional"))
      (node (ref "IC9") (pin "15") (pinfunction "SDA_15") (pintype "bidirectional"))
      (node (ref "R7") (pin "1") (pinfunction "1_1") (pintype "passive"))
      (node (ref "U2") (pin "43") (pinfunction "PB7_43") (pintype "bidirectional"))
      (node (ref "X0") (pin "3") (pinfunction "PA12/TWI0_SDA_3") (pintype "bidirectional"))
    )
    (net (code "33") (name "/SWCKL") (class "Default")
      (node (ref "SWD") (pin "3") (pinfunction "3_3") (pintype "passive"))
      (node (ref "U2") (pin "37") (pinfunction "PA14_37") (pintype "bidirectional"))
    )
    (net (code "34") (name "/SWDIO") (class "Default")
      (node (ref "SWD") (pin "2") (pinfunction "2_2") (pintype "passive"))
      (node (ref "U2") (pin "34") (pinfunction "PA13_34") (pintype "bidirectional"))
    )
    (net (code "35") (name "/TX") (class "Default")
      (node (ref "R1") (pin "1") (pinfunction "1_1") (pintype "passive"))
      (node (ref "U2") (pin "30") (pinfunction "PA9_30") (pintype "bidirectional"))
    )
    (net (code "36") (name "/VDD_OK") (class "Default")
      (node (ref "DD1") (pin "1") (pinfunction "~{RST}_1") (pintype "passive"))
    )
    (net (code "37") (name "/Z3V3") (class "Default")
      (node (ref "C19") (pin "1") (pinfunction "1_1") (pintype "passive"))
      (node (ref "C6") (pin "2") (pinfunction "2_2") (pintype "passive"))
      (node (ref "IC7") (pin "1") (pinfunction "VCC_1") (pintype "power_in"))
      (node (ref "OK1") (pin "6") (pinfunction "COL_6") (pintype "passive"))
      (node (ref "OK1") (pin "8") (pinfunction "COL_8") (pintype "passive"))
      (node (ref "OK2") (pin "6") (pinfunction "COL_6") (pintype "passive"))
      (node (ref "OK2") (pin "8") (pinfunction "COL_8") (pintype "passive"))
      (node (ref "OK9") (pin "6") (pinfunction "COL_6") (pintype "passive"))
      (node (ref "OK9") (pin "8") (pinfunction "COL_8") (pintype "passive"))
      (node (ref "R3") (pin "1") (pinfunction "1_1") (pintype "passive"))
      (node (ref "R34") (pin "2") (pinfunction "2_2") (pintype "passive"))
      (node (ref "R4") (pin "1") (pinfunction "1_1") (pintype "passive"))
      (node (ref "R6") (pin "2") (pinfunction "2_2") (pintype "passive"))
      (node (ref "R7") (pin "2") (pinfunction "2_2") (pintype "passive"))
      (node (ref "R72") (pin "1") (pinfunction "1_1") (pintype "passive"))
      (node (ref "X0") (pin "1") (pinfunction "3V3_1") (pintype "power_in"))
      (node (ref "X0") (pin "17") (pinfunction "3V3_17") (pintype "power_in"))
    )
    (net (code "38") (name "GND") (class "Default")
      (node (ref "1W-1") (pin "3") (pinfunction "K_3") (pintype "passive"))
      (node (ref "1W-2") (pin "3") (pinfunction "K_3") (pintype "passive"))
      (node (ref "C1") (pin "1") (pinfunction "1_1") (pintype "passive"))
      (node (ref "C10") (pin "1") (pinfunction "1_1") (pintype "passive"))
      (node (ref "C11") (pin "-") (pinfunction "-_-") (pintype "passive"))
      (node (ref "C12") (pin "-") (pinfunction "-_-") (pintype "passive"))
      (node (ref "C13") (pin "1") (pinfunction "1_1") (pintype "passive"))
      (node (ref "C14") (pin "-") (pinfunction "-_-") (pintype "passive"))
      (node (ref "C15") (pin "2") (pinfunction "2_2") (pintype "passive"))
      (node (ref "C17") (pin "1") (pinfunction "1_1") (pintype "passive"))
      (node (ref "C19") (pin "2") (pinfunction "2_2") (pintype "passive"))
      (node (ref "C2") (pin "2") (pinfunction "2_2") (pintype "passive"))
      (node (ref "C20") (pin "2") (pinfunction "2_2") (pintype "passive"))
      (node (ref "C21") (pin "-") (pinfunction "-_-") (pintype "passive"))
      (node (ref "C22") (pin "1") (pinfunction "1_1") (pintype "passive"))
      (node (ref "C23") (pin "-") (pinfunction "-_-") (pintype "passive"))
      (node (ref "C24") (pin "2") (pinfunction "2_2") (pintype "passive"))
      (node (ref "C25") (pin "-") (pinfunction "-_-") (pintype "passive"))
      (node (ref "C26") (pin "-") (pinfunction "-_-") (pintype "passive"))
      (node (ref "C27") (pin "-") (pinfunction "-_-") (pintype "passive"))
      (node (ref "C28") (pin "2") (pinfunction "2_2") (pintype "passive"))
      (node (ref "C29") (pin "2") (pinfunction "2_2") (pintype "passive"))
      (node (ref "C3") (pin "2") (pinfunction "2_2") (pintype "passive"))
      (node (ref "C30") (pin "-") (pinfunction "-_-") (pintype "passive"))
      (node (ref "C31") (pin "-") (pinfunction "-_-") (pintype "passive"))
      (node (ref "C32") (pin "1") (pinfunction "1_1") (pintype "passive"))
      (node (ref "C33") (pin "2") (pinfunction "2_2") (pintype "passive"))
      (node (ref "C34") (pin "1") (pinfunction "1_1") (pintype "passive"))
      (node (ref "C4") (pin "2") (pinfunction "2_2") (pintype "passive"))
      (node (ref "C5") (pin "1") (pinfunction "1_1") (pintype "passive"))
      (node (ref "C6") (pin "1") (pinfunction "1_1") (pintype "passive"))
      (node (ref "C7") (pin "2") (pinfunction "2_2") (pintype "passive"))
      (node (ref "C9") (pin "1") (pinfunction "1_1") (pintype "passive"))
      (node (ref "D14") (pin "A") (pinfunction "A_A") (pintype "passive"))
      (node (ref "D15") (pin "1") (pinfunction "A1_1") (pintype "passive"))
      (node (ref "D16") (pin "1") (pinfunction "A1_1") (pintype "passive"))
      (node (ref "DD1") (pin "3") (pinfunction "VSS_3") (pintype "passive"))
      (node (ref "I2C") (pin "3") (pinfunction "3_3") (pintype "passive"))
      (node (ref "IC2") (pin "2") (pinfunction "GND_2") (pintype "passive"))
      (node (ref "IC2") (pin "2@1") (pinfunction "GND_2@1") (pintype "passive"))
      (node (ref "IC4") (pin "2") (pinfunction "GND_2") (pintype "passive"))
      (node (ref "IC4") (pin "2@1") (pinfunction "GND_2@1") (pintype "passive"))
      (node (ref "IC5") (pin "1") (pinfunction "B_1") (pintype "bidirectional"))
      (node (ref "IC6") (pin "1") (pinfunction "GND_1") (pintype "power_in"))
      (node (ref "IC7") (pin "2") (pinfunction "GND_2") (pintype "power_in"))
      (node (ref "IC8") (pin "1") (pinfunction "B_1") (pintype "bidirectional"))
      (node (ref "IC9") (pin "8") (pinfunction "VSS_8") (pintype "power_in"))
      (node (ref "Q1") (pin "2") (pinfunction "S_2") (pintype "passive"))
      (node (ref "Q11") (pin "1") (pinfunction "S_1") (pintype "passive"))
      (node (ref "Q11") (pin "2") (pinfunction "S_2") (pintype "passive"))
      (node (ref "Q11") (pin "3") (pinfunction "S_3") (pintype "passive"))
      (node (ref "Q13") (pin "2") (pinfunction "S_2") (pintype "passive"))
      (node (ref "Q14") (pin "2") (pinfunction "S_2") (pintype "passive"))
      (node (ref "Q16") (pin "2") (pinfunction "S_2") (pintype "passive"))
      (node (ref "Q17") (pin "2") (pinfunction "S_2") (pintype "passive"))
      (node (ref "Q2") (pin "2") (pinfunction "S_2") (pintype "passive"))
      (node (ref "Q3") (pin "2") (pinfunction "S_2") (pintype "passive"))
      (node (ref "Q4") (pin "2") (pinfunction "S_2") (pintype "passive"))
      (node (ref "Q9") (pin "1") (pinfunction "S_1") (pintype "passive"))
      (node (ref "Q9") (pin "2") (pinfunction "S_2") (pintype "passive"))
      (node (ref "Q9") (pin "3") (pinfunction "S_3") (pintype "passive"))
      (node (ref "R10") (pin "1") (pinfunction "1_1") (pintype "passive"))
      (node (ref "R13") (pin "2") (pinfunction "2_2") (pintype "passive"))
      (node (ref "R27") (pin "1") (pinfunction "1_1") (pintype "passive"))
      (node (ref "R29") (pin "1") (pinfunction "1_1") (pintype "passive"))
      (node (ref "R33") (pin "2") (pinfunction "2_2") (pintype "passive"))
      (node (ref "R35") (pin "1") (pinfunction "1_1") (pintype "passive"))
      (node (ref "R37") (pin "2") (pinfunction "2_2") (pintype "passive"))
      (node (ref "R45") (pin "2") (pinfunction "2_2") (pintype "passive"))
      (node (ref "R49") (pin "2") (pinfunction "2_2") (pintype "passive"))
      (node (ref "R50") (pin "2") (pinfunction "2_2") (pintype "passive"))
      (node (ref "R51") (pin "2") (pinfunction "2_2") (pintype "passive"))
      (node (ref "R52") (pin "2") (pinfunction "2_2") (pintype "passive"))
      (node (ref "R53") (pin "2") (pinfunction "2_2") (pintype "passive"))
      (node (ref "R54") (pin "2") (pinfunction "2_2") (pintype "passive"))
      (node (ref "R55") (pin "2") (pinfunction "2_2") (pintype "passive"))
      (node (ref "R56") (pin "1") (pinfunction "1_1") (pintype "passive"))
      (node (ref "R57") (pin "1") (pinfunction "1_1") (pintype "passive"))
      (node (ref "R58") (pin "1") (pinfunction "1_1") (pintype "passive"))
      (node (ref "R59") (pin "2") (pinfunction "2_2") (pintype "passive"))
      (node (ref "R60") (pin "2") (pinfunction "2_2") (pintype "passive"))
      (node (ref "R61") (pin "2") (pinfunction "2_2") (pintype "passive"))
      (node (ref "R62") (pin "2") (pinfunction "2_2") (pintype "passive"))
      (node (ref "R66") (pin "2") (pinfunction "2_2") (pintype "passive"))
      (node (ref "R68") (pin "1") (pinfunction "1_1") (pintype "passive"))
      (node (ref "R70") (pin "2") (pinfunction "2_2") (pintype "passive"))
      (node (ref "R73") (pin "2") (pinfunction "2_2") (pintype "passive"))
      (node (ref "R76") (pin "2") (pinfunction "2_2") (pintype "passive"))
      (node (ref "SWD") (pin "4") (pinfunction "4_4") (pintype "passive"))
      (node (ref "U$10") (pin "3") (pinfunction "GND_3") (pintype "bidirectional"))
      (node (ref "U$11") (pin "3") (pinfunction "GND_3") (pintype "bidirectional"))
      (node (ref "U2") (pin "23") (pinfunction "VSS_1_23") (pintype "power_in"))
      (node (ref "U2") (pin "35") (pinfunction "VSS_2_35") (pintype "power_in"))
      (node (ref "U2") (pin "47") (pinfunction "VSS_3_47") (pintype "power_in"))
      (node (ref "U2") (pin "8") (pinfunction "VSSA_8") (pintype "power_in"))
      (node (ref "UART") (pin "3") (pinfunction "3_3") (pintype "passive"))
      (node (ref "UART2") (pin "3") (pinfunction "3_3") (pintype "passive"))
      (node (ref "X0") (pin "14") (pinfunction "GND_14") (pintype "power_in"))
      (node (ref "X0") (pin "20") (pinfunction "GND_20") (pintype "power_in"))
      (node (ref "X0") (pin "25") (pinfunction "GND_25") (pintype "power_in"))
      (node (ref "X0") (pin "6") (pinfunction "GND_6") (pintype "power_in"))
      (node (ref "X0") (pin "9") (pinfunction "GND_9") (pintype "power_in"))
      (node (ref "X13") (pin "1") (pinfunction "KL_1") (pintype "passive"))
      (node (ref "X14") (pin "1") (pinfunction "KL_1") (pintype "passive"))
      (node (ref "X15") (pin "2") (pinfunction "KL_2") (pintype "passive"))
      (node (ref "X4") (pin "2") (pinfunction "KL_2") (pintype "passive"))
      (node (ref "X7") (pin "1") (pinfunction "KL_1") (pintype "passive"))
      (node (ref "X9") (pin "3") (pinfunction "KL_3") (pintype "passive"))
    )
    (net (code "39") (name "Net-(1W-1A-K)") (class "Default")
      (node (ref "1W-1") (pin "1") (pinfunction "K_1") (pintype "passive"))
      (node (ref "L1W1") (pin "A") (pinfunction "A_A") (pintype "passive"))
      (node (ref "Q8") (pin "3") (pinfunction "D_3") (pintype "passive"))
    )
    (net (code "40") (name "Net-(1W-1B-K)") (class "Default")
      (node (ref "1W-1") (pin "2") (pinfunction "K_2") (pintype "passive"))
      (node (ref "D15") (pin "3") (pinfunction "C1A2_3") (pintype "passive"))
      (node (ref "IC5") (pin "4") (pinfunction "X_4") (pintype "bidirectional"))
    )
    (net (code "41") (name "Net-(1W-2A-K)") (class "Default")
      (node (ref "1W-2") (pin "1") (pinfunction "K_1") (pintype "passive"))
      (node (ref "L1W2") (pin "A") (pinfunction "A_A") (pintype "passive"))
      (node (ref "Q10") (pin "3") (pinfunction "D_3") (pintype "passive"))
    )
    (net (code "42") (name "Net-(1W-2B-K)") (class "Default")
      (node (ref "1W-2") (pin "2") (pinfunction "K_2") (pintype "passive"))
      (node (ref "D16") (pin "3") (pinfunction "C1A2_3") (pintype "passive"))
      (node (ref "IC8") (pin "4") (pinfunction "X_4") (pintype "bidirectional"))
    )
    (net (code "43") (name "Net-(C21-Pad+)") (class "Default")
      (node (ref "C21") (pin "+") (pinfunction "+_+") (pintype "passive"))
      (node (ref "K1") (pin "2") (pinfunction "2_2") (pintype "passive"))
      (node (ref "R26") (pin "2") (pinfunction "2_2") (pintype "passive"))
    )
    (net (code "44") (name "Net-(C25-Pad+)") (class "Default")
      (node (ref "C25") (pin "+") (pinfunction "+_+") (pintype "passive"))
      (node (ref "K6") (pin "2") (pinfunction "2_2") (pintype "passive"))
      (node (ref "R41") (pin "2") (pinfunction "2_2") (pintype "passive"))
    )
    (net (code "45") (name "Net-(IC1A-1W)") (class "Default")
      (node (ref "IC1") (pin "2") (pinfunction "1W_2") (pintype "open_collector"))
      (node (ref "IC5") (pin "3") (pinfunction "A_3") (pintype "bidirectional"))
      (node (ref "IC8") (pin "3") (pinfunction "A_3") (pintype "bidirectional"))
      (node (ref "Q7") (pin "3") (pinfunction "D_3") (pintype "passive"))
    )
    (net (code "46") (name "Net-(IC1A-PCT)") (class "Default")
      (node (ref "IC1") (pin "6") (pinfunction "PCT_6") (pintype "output"))
      (node (ref "Q7") (pin "1") (pinfunction "G_1") (pintype "passive"))
    )
    (net (code "47") (name "Net-(IC3-VIN+)") (class "Default")
      (node (ref "C18") (pin "2") (pinfunction "2_2") (pintype "passive"))
      (node (ref "FB2") (pin "1") (pinfunction "1_1") (pintype "passive"))
      (node (ref "IC3") (pin "2") (pinfunction "VIN+_2") (pintype "bidirectional"))
    )
    (net (code "48") (name "Net-(IC3-VIN-)") (class "Default")
      (node (ref "C18") (pin "1") (pinfunction "1_1") (pintype "passive"))
      (node (ref "IC3") (pin "1") (pinfunction "VIN-_1") (pintype "bidirectional"))
      (node (ref "Q1") (pin "3") (pinfunction "D_3") (pintype "passive"))
    )
    (net (code "49") (name "Net-(IC3-VOUT+)") (class "Default")
      (node (ref "C16") (pin "1") (pinfunction "1_1") (pintype "passive"))
      (node (ref "IC3") (pin "4") (pinfunction "VOUT+_4") (pintype "bidirectional"))
      (node (ref "R17") (pin "2") (pinfunction "2_2") (pintype "passive"))
      (node (ref "R65") (pin "1") (pinfunction "1_1") (pintype "passive"))
      (node (ref "R69") (pin "2") (pinfunction "2_2") (pintype "passive"))
      (node (ref "X13") (pin "3") (pinfunction "KL_3") (pintype "passive"))
    )
    (net (code "50") (name "Net-(IC3-VOUT-)") (class "Default")
      (node (ref "C16") (pin "2") (pinfunction "2_2") (pintype "passive"))
      (node (ref "IC3") (pin "3") (pinfunction "VOUT-_3") (pintype "bidirectional"))
      (node (ref "OK1") (pin "2") (pinfunction "C_2") (pintype "passive"))
      (node (ref "OK1") (pin "4") (pinfunction "C_4") (pintype "passive"))
      (node (ref "OK2") (pin "2") (pinfunction "C_2") (pintype "passive"))
      (node (ref "OK2") (pin "4") (pinfunction "C_4") (pintype "passive"))
      (node (ref "OK9") (pin "2") (pinfunction "C_2") (pintype "passive"))
      (node (ref "OK9") (pin "4") (pinfunction "C_4") (pintype "passive"))
      (node (ref "TVS1") (pin "A") (pinfunction "A_A") (pintype "passive"))
      (node (ref "TVS3") (pin "A") (pinfunction "A_A") (pintype "passive"))
      (node (ref "TVS4") (pin "A") (pinfunction "A_A") (pintype "passive"))
      (node (ref "TVS5") (pin "A") (pinfunction "A_A") (pintype "passive"))
      (node (ref "TVS6") (pin "A") (pinfunction "A_A") (pintype "passive"))
    )
    (net (code "51") (name "Net-(IC4-VO)") (class "Default")
      (node (ref "C17") (pin "2") (pinfunction "2_2") (pintype "passive"))
      (node (ref "C23") (pin "+") (pinfunction "+_+") (pintype "passive"))
      (node (ref "C3") (pin "1") (pinfunction "1_1") (pintype "passive"))
      (node (ref "FB1") (pin "1") (pinfunction "1_1") (pintype "passive"))
      (node (ref "IC4") (pin "1") (pinfunction "VO_1") (pintype "passive"))
      (node (ref "LED1") (pin "A") (pinfunction "A_A") (pintype "passive"))
      (node (ref "LED2") (pin "A") (pinfunction "A_A") (pintype "passive"))
      (node (ref "R14") (pin "2") (pinfunction "2_2") (pintype "passive"))
      (node (ref "R8") (pin "2") (pinfunction "2_2") (pintype "passive"))
      (node (ref "SWD") (pin "1") (pinfunction "1_1") (pintype "passive"))
      (node (ref "U2") (pin "24") (pinfunction "VDD_1_24") (pintype "power_in"))
      (node (ref "U2") (pin "36") (pinfunction "VDD_2_36") (pintype "power_in"))
      (node (ref "U2") (pin "48") (pinfunction "VDD_3_48") (pintype "power_in"))
    )
    (net (code "52") (name "Net-(IC6-BST)") (class "Default")
      (node (ref "C8") (pin "1") (pinfunction "1_1") (pintype "passive"))
      (node (ref "IC6") (pin "6") (pinfunction "BST_6") (pintype "input"))
    )
    (net (code "53") (name "Net-(IC6-FB)") (class "Default")
      (node (ref "IC6") (pin "4") (pinfunction "FB_4") (pintype "input"))
      (node (ref "R10") (pin "2") (pinfunction "2_2") (pintype "passive"))
      (node (ref "R11") (pin "2") (pinfunction "2_2") (pintype "passive"))
    )
    (net (code "54") (name "Net-(IC6-SW)") (class "Default")
      (node (ref "C8") (pin "2") (pinfunction "2_2") (pintype "passive"))
      (node (ref "IC6") (pin "2") (pinfunction "SW_2") (pintype "passive"))
      (node (ref "L4.7") (pin "P$1") (pinfunction "1_P$1") (pintype "passive"))
    )
    (net (code "55") (name "Net-(IC9-A0)") (class "Default")
      (node (ref "IC9") (pin "1") (pinfunction "A0_1") (pintype "input"))
      (node (ref "R56") (pin "2") (pinfunction "2_2") (pintype "passive"))
    )
    (net (code "56") (name "Net-(IC9-A1)") (class "Default")
      (node (ref "IC9") (pin "2") (pinfunction "A1_2") (pintype "input"))
      (node (ref "R57") (pin "2") (pinfunction "2_2") (pintype "passive"))
    )
    (net (code "57") (name "Net-(IC9-A2)") (class "Default")
      (node (ref "IC9") (pin "3") (pinfunction "A2_3") (pintype "input"))
      (node (ref "R58") (pin "2") (pinfunction "2_2") (pintype "passive"))
    )
    (net (code "58") (name "Net-(IC9-P4)") (class "Default")
      (node (ref "IC9") (pin "9") (pinfunction "P4_9") (pintype "bidirectional"))
      (node (ref "R40") (pin "2") (pinfunction "2_2") (pintype "passive"))
      (node (ref "R59") (pin "1") (pinfunction "1_1") (pintype "passive"))
    )
    (net (code "59") (name "Net-(IC9-P5)") (class "Default")
      (node (ref "IC9") (pin "10") (pinfunction "P5_10") (pintype "bidirectional"))
      (node (ref "R43") (pin "2") (pinfunction "2_2") (pintype "passive"))
      (node (ref "R60") (pin "1") (pinfunction "1_1") (pintype "passive"))
    )
    (net (code "60") (name "Net-(IC9-P6)") (class "Default")
      (node (ref "IC9") (pin "11") (pinfunction "P6_11") (pintype "bidirectional"))
      (node (ref "R44") (pin "2") (pinfunction "2_2") (pintype "passive"))
      (node (ref "R61") (pin "1") (pinfunction "1_1") (pintype "passive"))
    )
    (net (code "61") (name "Net-(IC9-P7)") (class "Default")
      (node (ref "IC9") (pin "12") (pinfunction "P7_12") (pintype "bidirectional"))
      (node (ref "R47") (pin "2") (pinfunction "2_2") (pintype "passive"))
      (node (ref "R62") (pin "1") (pinfunction "1_1") (pintype "passive"))
    )
    (net (code "62") (name "Net-(IC10A-I)") (class "Default")
      (node (ref "IC10") (pin "2") (pinfunction "I_2") (pintype "input"))
      (node (ref "OK2") (pin "5") (pinfunction "EMIT_5") (pintype "passive"))
      (node (ref "R51") (pin "1") (pinfunction "1_1") (pintype "passive"))
      (node (ref "R9") (pin "2") (pinfunction "2_2") (pintype "passive"))
    )
    (net (code "63") (name "Net-(IC10A-O)") (class "Default")
      (node (ref "IC10") (pin "4") (pinfunction "O_4") (pintype "output"))
      (node (ref "R46") (pin "2") (pinfunction "2_2") (pintype "passive"))
    )
    (net (code "64") (name "Net-(IC11A-I)") (class "Default")
      (node (ref "IC11") (pin "2") (pinfunction "I_2") (pintype "input"))
      (node (ref "OK2") (pin "7") (pinfunction "EMIT_7") (pintype "passive"))
      (node (ref "R21") (pin "2") (pinfunction "2_2") (pintype "passive"))
      (node (ref "R52") (pin "1") (pinfunction "1_1") (pintype "passive"))
    )
    (net (code "65") (name "Net-(IC11A-O)") (class "Default")
      (node (ref "IC11") (pin "4") (pinfunction "O_4") (pintype "output"))
      (node (ref "R48") (pin "2") (pinfunction "2_2") (pintype "passive"))
    )
    (net (code "66") (name "Net-(IC12A-I)") (class "Default")
      (node (ref "IC12") (pin "2") (pinfunction "I_2") (pintype "input"))
      (node (ref "OK9") (pin "5") (pinfunction "EMIT_5") (pintype "passive"))
      (node (ref "R24") (pin "2") (pinfunction "2_2") (pintype "passive"))
      (node (ref "R55") (pin "1") (pinfunction "1_1") (pintype "passive"))
    )
    (net (code "67") (name "Net-(IC12A-O)") (class "Default")
      (node (ref "IC12") (pin "4") (pinfunction "O_4") (pintype "output"))
      (node (ref "R63") (pin "2") (pinfunction "2_2") (pintype "passive"))
    )
    (net (code "68") (name "Net-(K2A-PA)") (class "Default")
      (node (ref "K2") (pin "3") (pinfunction "PA_3") (pintype "passive"))
      (node (ref "K2") (pin "6") (pinfunction "PB_6") (pintype "passive"))
      (node (ref "X1") (pin "1") (pinfunction "KL_1") (pintype "passive"))
    )
    (net (code "69") (name "Net-(K2A-SA)") (class "Default")
      (node (ref "K2") (pin "4") (pinfunction "SA_4") (pintype "passive"))
      (node (ref "K2") (pin "5") (pinfunction "SB_5") (pintype "passive"))
      (node (ref "X1") (pin "2") (pinfunction "KL_2") (pintype "passive"))
    )
    (net (code "70") (name "Net-(K2B-2)") (class "Default")
      (node (ref "C27") (pin "+") (pinfunction "+_+") (pintype "passive"))
      (node (ref "K2") (pin "8") (pinfunction "2_8") (pintype "passive"))
      (node (ref "R74") (pin "2") (pinfunction "2_2") (pintype "passive"))
    )
    (net (code "71") (name "Net-(K3A-PA)") (class "Default")
      (node (ref "K3") (pin "3") (pinfunction "PA_3") (pintype "passive"))
      (node (ref "K3") (pin "6") (pinfunction "PB_6") (pintype "passive"))
      (node (ref "X2") (pin "1") (pinfunction "KL_1") (pintype "passive"))
    )
    (net (code "72") (name "Net-(K3A-SA)") (class "Default")
      (node (ref "K3") (pin "4") (pinfunction "SA_4") (pintype "passive"))
      (node (ref "K3") (pin "5") (pinfunction "SB_5") (pintype "passive"))
      (node (ref "X2") (pin "2") (pinfunction "KL_2") (pintype "passive"))
    )
    (net (code "73") (name "Net-(K3B-2)") (class "Default")
      (node (ref "C26") (pin "+") (pinfunction "+_+") (pintype "passive"))
      (node (ref "K3") (pin "8") (pinfunction "2_8") (pintype "passive"))
      (node (ref "R82") (pin "2") (pinfunction "2_2") (pintype "passive"))
    )
    (net (code "74") (name "Net-(K4A-PA)") (class "Default")
      (node (ref "K4") (pin "3") (pinfunction "PA_3") (pintype "passive"))
      (node (ref "K4") (pin "6") (pinfunction "PB_6") (pintype "passive"))
      (node (ref "X3") (pin "1") (pinfunction "KL_1") (pintype "passive"))
    )
    (net (code "75") (name "Net-(K4A-SA)") (class "Default")
      (node (ref "K4") (pin "4") (pinfunction "SA_4") (pintype "passive"))
      (node (ref "K4") (pin "5") (pinfunction "SB_5") (pintype "passive"))
      (node (ref "X3") (pin "2") (pinfunction "KL_2") (pintype "passive"))
    )
    (net (code "76") (name "Net-(K4B-2)") (class "Default")
      (node (ref "C30") (pin "+") (pinfunction "+_+") (pintype "passive"))
      (node (ref "K4") (pin "8") (pinfunction "2_8") (pintype "passive"))
      (node (ref "R85") (pin "2") (pinfunction "2_2") (pintype "passive"))
    )
    (net (code "77") (name "Net-(K5A-PA)") (class "Default")
      (node (ref "K5") (pin "3") (pinfunction "PA_3") (pintype "passive"))
      (node (ref "K5") (pin "6") (pinfunction "PB_6") (pintype "passive"))
      (node (ref "X5") (pin "1") (pinfunction "KL_1") (pintype "passive"))
    )
    (net (code "78") (name "Net-(K5A-SA)") (class "Default")
      (node (ref "K5") (pin "4") (pinfunction "SA_4") (pintype "passive"))
      (node (ref "K5") (pin "5") (pinfunction "SB_5") (pintype "passive"))
      (node (ref "X5") (pin "2") (pinfunction "KL_2") (pintype "passive"))
    )
    (net (code "79") (name "Net-(K5B-2)") (class "Default")
      (node (ref "C31") (pin "+") (pinfunction "+_+") (pintype "passive"))
      (node (ref "K5") (pin "8") (pinfunction "2_8") (pintype "passive"))
      (node (ref "R88") (pin "2") (pinfunction "2_2") (pintype "passive"))
    )
    (net (code "80") (name "Net-(L1W1-PadC)") (class "Default")
      (node (ref "L1W1") (pin "C") (pinfunction "C_C") (pintype "passive"))
      (node (ref "R76") (pin "1") (pinfunction "1_1") (pintype "passive"))
    )
    (net (code "81") (name "Net-(L1W2-PadC)") (class "Default")
      (node (ref "L1W2") (pin "C") (pinfunction "C_C") (pintype "passive"))
      (node (ref "R45") (pin "1") (pinfunction "1_1") (pintype "passive"))
    )
    (net (code "82") (name "Net-(L4.7-2)") (class "Default")
      (node (ref "C14") (pin "+") (pinfunction "+_+") (pintype "passive"))
      (node (ref "C22") (pin "2") (pinfunction "2_2") (pintype "passive"))
      (node (ref "C9") (pin "2") (pinfunction "2_2") (pintype "passive"))
      (node (ref "L4.7") (pin "P$2") (pinfunction "2_P$2") (pintype "passive"))
      (node (ref "R11") (pin "1") (pinfunction "1_1") (pintype "passive"))
      (node (ref "R5") (pin "2") (pinfunction "2_2") (pintype "passive"))
      (node (ref "X0") (pin "2") (pinfunction "5V_2") (pintype "power_in"))
      (node (ref "X0") (pin "4") (pinfunction "5V_4") (pintype "power_in"))
    )
    (net (code "83") (name "Net-(LED1-PadC)") (class "Default")
      (node (ref "LED1") (pin "C") (pinfunction "C_C") (pintype "passive"))
      (node (ref "R22") (pin "1") (pinfunction "1_1") (pintype "passive"))
    )
    (net (code "84") (name "Net-(LED2-PadC)") (class "Default")
      (node (ref "LED2") (pin "C") (pinfunction "C_C") (pintype "passive"))
      (node (ref "R23") (pin "1") (pinfunction "1_1") (pintype "passive"))
    )
    (net (code "85") (name "Net-(LED3-PadC)") (class "Default")
      (node (ref "LED3") (pin "C") (pinfunction "C_C") (pintype "passive"))
      (node (ref "R75") (pin "1") (pinfunction "1_1") (pintype "passive"))
    )
    (net (code "86") (name "Net-(LED4-PadC)") (class "Default")
      (node (ref "LED4") (pin "C") (pinfunction "C_C") (pintype "passive"))
      (node (ref "R83") (pin "1") (pinfunction "1_1") (pintype "passive"))
    )
    (net (code "87") (name "Net-(LED5-PadC)") (class "Default")
      (node (ref "LED5") (pin "C") (pinfunction "C_C") (pintype "passive"))
      (node (ref "R86") (pin "1") (pinfunction "1_1") (pintype "passive"))
    )
    (net (code "88") (name "Net-(LED6-PadC)") (class "Default")
      (node (ref "LED6") (pin "C") (pinfunction "C_C") (pintype "passive"))
      (node (ref "R89") (pin "1") (pinfunction "1_1") (pintype "passive"))
    )
    (net (code "89") (name "Net-(LED7-PadC)") (class "Default")
      (node (ref "LED7") (pin "C") (pinfunction "C_C") (pintype "passive"))
      (node (ref "R36") (pin "1") (pinfunction "1_1") (pintype "passive"))
    )
    (net (code "90") (name "Net-(LED8-PadC)") (class "Default")
      (node (ref "LED8") (pin "C") (pinfunction "C_C") (pintype "passive"))
      (node (ref "R42") (pin "1") (pinfunction "1_1") (pintype "passive"))
    )
    (net (code "91") (name "Net-(LED9-PadC)") (class "Default")
      (node (ref "LED9") (pin "C") (pinfunction "C_C") (pintype "passive"))
      (node (ref "R25") (pin "1") (pinfunction "1_1") (pintype "passive"))
    )
    (net (code "92") (name "Net-(LED10-PadC)") (class "Default")
      (node (ref "LED10") (pin "C") (pinfunction "C_C") (pintype "passive"))
      (node (ref "R64") (pin "1") (pinfunction "1_1") (pintype "passive"))
    )
    (net (code "93") (name "Net-(OK1A-A)") (class "Default")
      (node (ref "OK1") (pin "1") (pinfunction "A_1") (pintype "passive"))
      (node (ref "R16") (pin "2") (pinfunction "2_2") (pintype "passive"))
    )
    (net (code "94") (name "Net-(OK1B-A)") (class "Default")
      (node (ref "OK1") (pin "3") (pinfunction "A_3") (pintype "passive"))
      (node (ref "R15") (pin "2") (pinfunction "2_2") (pintype "passive"))
    )
    (net (code "95") (name "Net-(OK2A-A)") (class "Default")
      (node (ref "OK2") (pin "1") (pinfunction "A_1") (pintype "passive"))
      (node (ref "R19") (pin "2") (pinfunction "2_2") (pintype "passive"))
    )
    (net (code "96") (name "Net-(OK2B-A)") (class "Default")
      (node (ref "OK2") (pin "3") (pinfunction "A_3") (pintype "passive"))
      (node (ref "R18") (pin "2") (pinfunction "2_2") (pintype "passive"))
    )
    (net (code "97") (name "Net-(OK9A-A)") (class "Default")
      (node (ref "OK9") (pin "1") (pinfunction "A_1") (pintype "passive"))
      (node (ref "R20") (pin "2") (pinfunction "2_2") (pintype "passive"))
    )
    (net (code "98") (name "Net-(OK9B-A)") (class "Default")
      (node (ref "OK9") (pin "3") (pinfunction "A_3") (pintype "passive"))
      (node (ref "R65") (pin "2") (pinfunction "2_2") (pintype "passive"))
    )
    (net (code "99") (name "Net-(Q1-G)") (class "Default")
      (node (ref "Q1") (pin "1") (pinfunction "G_1") (pintype "passive"))
      (node (ref "R67") (pin "1") (pinfunction "1_1") (pintype "passive"))
    )
    (net (code "100") (name "Net-(Q2-D)") (class "Default")
      (node (ref "Q2") (pin "3") (pinfunction "D_3") (pintype "passive"))
      (node (ref "R28") (pin "1") (pinfunction "1_1") (pintype "passive"))
    )
    (net (code "101") (name "Net-(Q2-G)") (class "Default")
      (node (ref "Q2") (pin "1") (pinfunction "G_1") (pintype "passive"))
      (node (ref "R71") (pin "2") (pinfunction "2_2") (pintype "passive"))
    )
    (net (code "102") (name "Net-(Q3-D)") (class "Default")
      (node (ref "D1") (pin "A") (pinfunction "A_A") (pintype "passive"))
      (node (ref "K1") (pin "1") (pinfunction "1_1") (pintype "passive"))
      (node (ref "Q3") (pin "3") (pinfunction "D_3") (pintype "passive"))
      (node (ref "R36") (pin "2") (pinfunction "2_2") (pintype "passive"))
    )
    (net (code "103") (name "Net-(Q3-G)") (class "Default")
      (node (ref "Q3") (pin "1") (pinfunction "G_1") (pintype "passive"))
      (node (ref "R40") (pin "1") (pinfunction "1_1") (pintype "passive"))
    )
    (net (code "104") (name "Net-(Q4-D)") (class "Default")
      (node (ref "D2") (pin "A") (pinfunction "A_A") (pintype "passive"))
      (node (ref "K6") (pin "1") (pinfunction "1_1") (pintype "passive"))
      (node (ref "Q4") (pin "3") (pinfunction "D_3") (pintype "passive"))
      (node (ref "R42") (pin "2") (pinfunction "2_2") (pintype "passive"))
    )
    (net (code "105") (name "Net-(Q4-G)") (class "Default")
      (node (ref "Q4") (pin "1") (pinfunction "G_1") (pintype "passive"))
      (node (ref "R43") (pin "1") (pinfunction "1_1") (pintype "passive"))
    )
    (net (code "106") (name "Net-(Q8-G)") (class "Default")
      (node (ref "Q8") (pin "1") (pinfunction "G_1") (pintype "passive"))
      (node (ref "R31") (pin "2") (pinfunction "2_2") (pintype "passive"))
    )
    (net (code "107") (name "Net-(Q9-G)") (class "Default")
      (node (ref "Q9") (pin "4") (pinfunction "G_4") (pintype "passive"))
      (node (ref "R44") (pin "1") (pinfunction "1_1") (pintype "passive"))
    )
    (net (code "108") (name "Net-(Q10-G)") (class "Default")
      (node (ref "Q10") (pin "1") (pinfunction "G_1") (pintype "passive"))
      (node (ref "R32") (pin "2") (pinfunction "2_2") (pintype "passive"))
    )
    (net (code "109") (name "Net-(Q11-G)") (class "Default")
      (node (ref "Q11") (pin "4") (pinfunction "G_4") (pintype "passive"))
      (node (ref "R47") (pin "1") (pinfunction "1_1") (pintype "passive"))
    )
    (net (code "110") (name "Net-(Q13-D)") (class "Default")
      (node (ref "D19") (pin "A") (pinfunction "A_A") (pintype "passive"))
      (node (ref "K2") (pin "1") (pinfunction "1_1") (pintype "passive"))
      (node (ref "Q13") (pin "3") (pinfunction "D_3") (pintype "passive"))
      (node (ref "R75") (pin "2") (pinfunction "2_2") (pintype "passive"))
    )
    (net (code "111") (name "Net-(Q13-G)") (class "Default")
      (node (ref "Q13") (pin "1") (pinfunction "G_1") (pintype "passive"))
      (node (ref "R77") (pin "1") (pinfunction "1_1") (pintype "passive"))
    )
    (net (code "112") (name "Net-(Q14-D)") (class "Default")
      (node (ref "D21") (pin "A") (pinfunction "A_A") (pintype "passive"))
      (node (ref "K3") (pin "1") (pinfunction "1_1") (pintype "passive"))
      (node (ref "Q14") (pin "3") (pinfunction "D_3") (pintype "passive"))
      (node (ref "R83") (pin "2") (pinfunction "2_2") (pintype "passive"))
    )
    (net (code "113") (name "Net-(Q14-G)") (class "Default")
      (node (ref "Q14") (pin "1") (pinfunction "G_1") (pintype "passive"))
      (node (ref "R84") (pin "1") (pinfunction "1_1") (pintype "passive"))
    )
    (net (code "114") (name "Net-(Q16-D)") (class "Default")
      (node (ref "D22") (pin "A") (pinfunction "A_A") (pintype "passive"))
      (node (ref "K4") (pin "1") (pinfunction "1_1") (pintype "passive"))
      (node (ref "Q16") (pin "3") (pinfunction "D_3") (pintype "passive"))
      (node (ref "R86") (pin "2") (pinfunction "2_2") (pintype "passive"))
    )
    (net (code "115") (name "Net-(Q16-G)") (class "Default")
      (node (ref "Q16") (pin "1") (pinfunction "G_1") (pintype "passive"))
      (node (ref "R87") (pin "1") (pinfunction "1_1") (pintype "passive"))
    )
    (net (code "116") (name "Net-(Q17-D)") (class "Default")
      (node (ref "D23") (pin "A") (pinfunction "A_A") (pintype "passive"))
      (node (ref "K5") (pin "1") (pinfunction "1_1") (pintype "passive"))
      (node (ref "Q17") (pin "3") (pinfunction "D_3") (pintype "passive"))
      (node (ref "R89") (pin "2") (pinfunction "2_2") (pintype "passive"))
    )
    (net (code "117") (name "Net-(Q17-G)") (class "Default")
      (node (ref "Q17") (pin "1") (pinfunction "G_1") (pintype "passive"))
      (node (ref "R90") (pin "1") (pinfunction "1_1") (pintype "passive"))
    )
    (net (code "118") (name "Net-(U$10-OUTF1)") (class "Default")
      (node (ref "U$10") (pin "5") (pinfunction "OUTF1_5") (pintype "bidirectional"))
      (node (ref "U$10") (pin "6") (pinfunction "OUTF2_6") (pintype "bidirectional"))
      (node (ref "X4") (pin "3") (pinfunction "KL_3") (pintype "passive"))
    )
    (net (code "119") (name "Net-(U$10-OUTR1)") (class "Default")
      (node (ref "U$10") (pin "7") (pinfunction "OUTR1_7") (pintype "bidirectional"))
      (node (ref "U$10") (pin "8") (pinfunction "OUTR2_8") (pintype "bidirectional"))
      (node (ref "X4") (pin "1") (pinfunction "KL_1") (pintype "passive"))
    )
    (net (code "120") (name "Net-(U$11-OUTF1)") (class "Default")
      (node (ref "U$11") (pin "5") (pinfunction "OUTF1_5") (pintype "bidirectional"))
      (node (ref "U$11") (pin "6") (pinfunction "OUTF2_6") (pintype "bidirectional"))
      (node (ref "X15") (pin "3") (pinfunction "KL_3") (pintype "passive"))
    )
    (net (code "121") (name "Net-(U$11-OUTR1)") (class "Default")
      (node (ref "U$11") (pin "7") (pinfunction "OUTR1_7") (pintype "bidirectional"))
      (node (ref "U$11") (pin "8") (pinfunction "OUTR2_8") (pintype "bidirectional"))
      (node (ref "X15") (pin "1") (pinfunction "KL_1") (pintype "passive"))
    )
    (net (code "122") (name "Net-(U2-VBAT)") (class "Default")
      (node (ref "C2") (pin "1") (pinfunction "1_1") (pintype "passive"))
      (node (ref "FB1") (pin "2") (pinfunction "2_2") (pintype "passive"))
      (node (ref "U2") (pin "1") (pinfunction "VBAT_1") (pintype "power_in"))
      (node (ref "U2") (pin "9") (pinfunction "VDDA_9") (pintype "power_in"))
    )
    (net (code "123") (name "Net-(X0-PWM1{slash}PA06)") (class "Default")
      (node (ref "R70") (pin "1") (pinfunction "1_1") (pintype "passive"))
      (node (ref "R71") (pin "1") (pinfunction "1_1") (pintype "passive"))
      (node (ref "X0") (pin "7") (pinfunction "PWM1/PA06_7") (pintype "bidirectional"))
    )
    (net (code "124") (name "Net-(X0-UART1_RX{slash}PG07)") (class "Default")
      (node (ref "R1") (pin "2") (pinfunction "2_2") (pintype "passive"))
      (node (ref "R3") (pin "2") (pinfunction "2_2") (pintype "passive"))
      (node (ref "UART") (pin "2") (pinfunction "2_2") (pintype "passive"))
      (node (ref "X0") (pin "10") (pinfunction "UART1_RX/PG07_10") (pintype "bidirectional"))
    )
    (net (code "125") (name "Net-(X0-UART1_TX{slash}PG06)") (class "Default")
      (node (ref "R2") (pin "2") (pinfunction "2_2") (pintype "passive"))
      (node (ref "R4") (pin "2") (pinfunction "2_2") (pintype "passive"))
      (node (ref "UART") (pin "1") (pinfunction "1_1") (pintype "passive"))
      (node (ref "X0") (pin "8") (pinfunction "UART1_TX/PG06_8") (pintype "bidirectional"))
    )
    (net (code "126") (name "Net-(X0-UART2_RX{slash}PA01)") (class "Default")
      (node (ref "UART2") (pin "2") (pinfunction "2_2") (pintype "passive"))
      (node (ref "X0") (pin "11") (pinfunction "UART2_RX/PA01_11") (pintype "bidirectional"))
    )
    (net (code "127") (name "Net-(X0-UART2_TX{slash}PA00)") (class "Default")
      (node (ref "UART2") (pin "1") (pinfunction "1_1") (pintype "passive"))
      (node (ref "X0") (pin "13") (pinfunction "UART2_TX/PA00_13") (pintype "bidirectional"))
    )
    (net (code "128") (name "Net-(X6A-KL)") (class "Default")
      (node (ref "K1") (pin "O") (pinfunction "O_O") (pintype "passive"))
      (node (ref "X6") (pin "1") (pinfunction "KL_1") (pintype "passive"))
    )
    (net (code "129") (name "Net-(X6B-KL)") (class "Default")
      (node (ref "K1") (pin "P") (pinfunction "P_P") (pintype "passive"))
      (node (ref "X6") (pin "2") (pinfunction "KL_2") (pintype "passive"))
    )
    (net (code "130") (name "Net-(X6C-KL)") (class "Default")
      (node (ref "K1") (pin "S") (pinfunction "S_S") (pintype "passive"))
      (node (ref "X6") (pin "3") (pinfunction "KL_3") (pintype "passive"))
    )
    (net (code "131") (name "Net-(X7B-KL)") (class "Default")
      (node (ref "R18") (pin "1") (pinfunction "1_1") (pintype "passive"))
      (node (ref "TVS5") (pin "C") (pinfunction "C_C") (pintype "passive"))
      (node (ref "X7") (pin "2") (pinfunction "KL_2") (pintype "passive"))
    )
    (net (code "132") (name "Net-(X7C-KL)") (class "Default")
      (node (ref "R19") (pin "1") (pinfunction "1_1") (pintype "passive"))
      (node (ref "TVS6") (pin "C") (pinfunction "C_C") (pintype "passive"))
      (node (ref "X7") (pin "3") (pinfunction "KL_3") (pintype "passive"))
    )
    (net (code "133") (name "Net-(X7D-KL)") (class "Default")
      (node (ref "R69") (pin "1") (pinfunction "1_1") (pintype "passive"))
      (node (ref "X7") (pin "4") (pinfunction "KL_4") (pintype "passive"))
    )
    (net (code "134") (name "Net-(X8A-KL)") (class "Default")
      (node (ref "K6") (pin "O") (pinfunction "O_O") (pintype "passive"))
      (node (ref "X8") (pin "1") (pinfunction "KL_1") (pintype "passive"))
    )
    (net (code "135") (name "Net-(X8B-KL)") (class "Default")
      (node (ref "K6") (pin "P") (pinfunction "P_P") (pintype "passive"))
      (node (ref "X8") (pin "2") (pinfunction "KL_2") (pintype "passive"))
    )
    (net (code "136") (name "Net-(X8C-KL)") (class "Default")
      (node (ref "K6") (pin "S") (pinfunction "S_S") (pintype "passive"))
      (node (ref "X8") (pin "3") (pinfunction "KL_3") (pintype "passive"))
    )
    (net (code "137") (name "Net-(X9A-KL)") (class "Default")
      (node (ref "D10") (pin "A") (pinfunction "A_A") (pintype "passive"))
      (node (ref "R30") (pin "1") (pinfunction "1_1") (pintype "passive"))
      (node (ref "X9") (pin "1") (pinfunction "KL_1") (pintype "passive"))
    )
    (net (code "138") (name "Net-(X9B-KL)") (class "Default")
      (node (ref "D5") (pin "A") (pinfunction "A_A") (pintype "passive"))
      (node (ref "X9") (pin "2") (pinfunction "KL_2") (pintype "passive"))
    )
    (net (code "139") (name "Net-(X10B-KL)") (class "Default")
      (node (ref "D3") (pin "A") (pinfunction "A_A") (pintype "passive"))
      (node (ref "Q9") (pin "5") (pinfunction "D_5") (pintype "passive"))
      (node (ref "Q9") (pin "6") (pinfunction "D_6") (pintype "passive"))
      (node (ref "Q9") (pin "7") (pinfunction "D_7") (pintype "passive"))
      (node (ref "Q9") (pin "8") (pinfunction "D_8") (pintype "passive"))
      (node (ref "R25") (pin "2") (pinfunction "2_2") (pintype "passive"))
      (node (ref "X10") (pin "2") (pinfunction "KL_2") (pintype "passive"))
    )
    (net (code "140") (name "Net-(X11B-KL)") (class "Default")
      (node (ref "D4") (pin "A") (pinfunction "A_A") (pintype "passive"))
      (node (ref "Q11") (pin "5") (pinfunction "D_5") (pintype "passive"))
      (node (ref "Q11") (pin "6") (pinfunction "D_6") (pintype "passive"))
      (node (ref "Q11") (pin "7") (pinfunction "D_7") (pintype "passive"))
      (node (ref "Q11") (pin "8") (pinfunction "D_8") (pintype "passive"))
      (node (ref "R64") (pin "2") (pinfunction "2_2") (pintype "passive"))
      (node (ref "X11") (pin "2") (pinfunction "KL_2") (pintype "passive"))
    )
    (net (code "141") (name "Net-(X13B-KL)") (class "Default")
      (node (ref "R20") (pin "1") (pinfunction "1_1") (pintype "passive"))
      (node (ref "TVS1") (pin "C") (pinfunction "C_C") (pintype "passive"))
      (node (ref "X13") (pin "2") (pinfunction "KL_2") (pintype "passive"))
    )
    (net (code "142") (name "Net-(X14B-KL)") (class "Default")
      (node (ref "R15") (pin "1") (pinfunction "1_1") (pintype "passive"))
      (node (ref "TVS3") (pin "C") (pinfunction "C_C") (pintype "passive"))
      (node (ref "X14") (pin "2") (pinfunction "KL_2") (pintype "passive"))
    )
    (net (code "143") (name "Net-(X14C-KL)") (class "Default")
      (node (ref "R16") (pin "1") (pinfunction "1_1") (pintype "passive"))
      (node (ref "TVS4") (pin "C") (pinfunction "C_C") (pintype "passive"))
      (node (ref "X14") (pin "3") (pinfunction "KL_3") (pintype "passive"))
    )
    (net (code "144") (name "Net-(X14D-KL)") (class "Default")
      (node (ref "R17") (pin "1") (pinfunction "1_1") (pintype "passive"))
      (node (ref "X14") (pin "4") (pinfunction "KL_4") (pintype "passive"))
    )
    (net (code "145") (name "VDD") (class "Default")
      (node (ref "C20") (pin "1") (pinfunction "1_1") (pintype "passive"))
      (node (ref "C24") (pin "1") (pinfunction "1_1") (pintype "passive"))
      (node (ref "C32") (pin "2") (pinfunction "2_2") (pintype "passive"))
      (node (ref "C4") (pin "1") (pinfunction "1_1") (pintype "passive"))
      (node (ref "C7") (pin "1") (pinfunction "1_1") (pintype "passive"))
      (node (ref "D14") (pin "C") (pinfunction "C_C") (pintype "passive"))
      (node (ref "D15") (pin "2") (pinfunction "C2_2") (pintype "passive"))
      (node (ref "D16") (pin "2") (pinfunction "C2_2") (pintype "passive"))
      (node (ref "DD1") (pin "2") (pinfunction "VDD_2") (pintype "input"))
      (node (ref "IC2") (pin "3") (pinfunction "VI_3") (pintype "input"))
      (node (ref "IC9") (pin "16") (pinfunction "VDD_16") (pintype "power_in"))
      (node (ref "Q10") (pin "2") (pinfunction "S_2") (pintype "passive"))
      (node (ref "Q7") (pin "2") (pinfunction "S_2") (pintype "passive"))
      (node (ref "Q8") (pin "2") (pinfunction "S_2") (pintype "passive"))
      (node (ref "R27") (pin "2") (pinfunction "2_2") (pintype "passive"))
      (node (ref "R38") (pin "2") (pinfunction "2_2") (pintype "passive"))
      (node (ref "R39") (pin "2") (pinfunction "2_2") (pintype "passive"))
    )
    (net (code "146") (name "unconnected-(IC7-NC-Pad3)") (class "Default")
      (node (ref "IC7") (pin "3") (pinfunction "NC_3") (pintype "no_connect"))
    )
    (net (code "147") (name "unconnected-(IC9-~{INT}-Pad13)") (class "Default")
      (node (ref "IC9") (pin "13") (pinfunction "~{INT}_13") (pintype "output"))
    )
    (net (code "148") (name "unconnected-(K2A-OA-Pad2)") (class "Default")
      (node (ref "K2") (pin "2") (pinfunction "OA_2") (pintype "passive"))
    )
    (net (code "149") (name "unconnected-(K2A-OB-Pad7)") (class "Default")
      (node (ref "K2") (pin "7") (pinfunction "OB_7") (pintype "passive"))
    )
    (net (code "150") (name "unconnected-(K3A-OA-Pad2)") (class "Default")
      (node (ref "K3") (pin "2") (pinfunction "OA_2") (pintype "passive"))
    )
    (net (code "151") (name "unconnected-(K3A-OB-Pad7)") (class "Default")
      (node (ref "K3") (pin "7") (pinfunction "OB_7") (pintype "passive"))
    )
    (net (code "152") (name "unconnected-(K4A-OA-Pad2)") (class "Default")
      (node (ref "K4") (pin "2") (pinfunction "OA_2") (pintype "passive"))
    )
    (net (code "153") (name "unconnected-(K4A-OB-Pad7)") (class "Default")
      (node (ref "K4") (pin "7") (pinfunction "OB_7") (pintype "passive"))
    )
    (net (code "154") (name "unconnected-(K5A-OA-Pad2)") (class "Default")
      (node (ref "K5") (pin "2") (pinfunction "OA_2") (pintype "passive"))
    )
    (net (code "155") (name "unconnected-(K5A-OB-Pad7)") (class "Default")
      (node (ref "K5") (pin "7") (pinfunction "OB_7") (pintype "passive"))
    )
    (net (code "156") (name "unconnected-(U$10-INF-Pad2)") (class "Default")
      (node (ref "U$10") (pin "2") (pinfunction "INF_2") (pintype "bidirectional"))
    )
    (net (code "157") (name "unconnected-(U$10-INR-Pad1)") (class "Default")
      (node (ref "U$10") (pin "1") (pinfunction "INR_1") (pintype "bidirectional"))
    )
    (net (code "158") (name "unconnected-(U$11-INF-Pad2)") (class "Default")
      (node (ref "U$11") (pin "2") (pinfunction "INF_2") (pintype "bidirectional"))
    )
    (net (code "159") (name "unconnected-(U$11-INR-Pad1)") (class "Default")
      (node (ref "U$11") (pin "1") (pinfunction "INR_1") (pintype "bidirectional"))
    )
    (net (code "160") (name "unconnected-(U2-BOOT0-Pad44)") (class "Default")
      (node (ref "U2") (pin "44") (pinfunction "BOOT0_44") (pintype "input"))
    )
    (net (code "161") (name "unconnected-(U2-PA7-Pad17)") (class "Default")
      (node (ref "U2") (pin "17") (pinfunction "PA7_17") (pintype "bidirectional"))
    )
    (net (code "162") (name "unconnected-(U2-PA8-Pad29)") (class "Default")
      (node (ref "U2") (pin "29") (pinfunction "PA8_29") (pintype "bidirectional"))
    )
    (net (code "163") (name "unconnected-(U2-PB0-Pad18)") (class "Default")
      (node (ref "U2") (pin "18") (pinfunction "PB0_18") (pintype "bidirectional"))
    )
    (net (code "164") (name "unconnected-(U2-PB1-Pad19)") (class "Default")
      (node (ref "U2") (pin "19") (pinfunction "PB1_19") (pintype "bidirectional"))
    )
    (net (code "165") (name "unconnected-(U2-PB2-Pad20)") (class "Default")
      (node (ref "U2") (pin "20") (pinfunction "PB2_20") (pintype "bidirectional"))
    )
    (net (code "166") (name "unconnected-(U2-PB3-Pad39)") (class "Default")
      (node (ref "U2") (pin "39") (pinfunction "PB3_39") (pintype "bidirectional"))
    )
    (net (code "167") (name "unconnected-(U2-PB4-Pad40)") (class "Default")
      (node (ref "U2") (pin "40") (pinfunction "PB4_40") (pintype "bidirectional"))
    )
    (net (code "168") (name "unconnected-(U2-PC13-TAMPER-RTC-Pad2)") (class "Default")
      (node (ref "U2") (pin "2") (pinfunction "PC13-TAMPER-RTC_2") (pintype "bidirectional"))
    )
    (net (code "169") (name "unconnected-(U2-PC14-OSC32_IN-Pad3)") (class "Default")
      (node (ref "U2") (pin "3") (pinfunction "PC14-OSC32_IN_3") (pintype "bidirectional"))
    )
    (net (code "170") (name "unconnected-(U2-PC15-OSC32_OUT-Pad4)") (class "Default")
      (node (ref "U2") (pin "4") (pinfunction "PC15-OSC32_OUT_4") (pintype "bidirectional"))
    )
    (net (code "171") (name "unconnected-(U2-PD0-OSC_IN-Pad5)") (class "Default")
      (node (ref "U2") (pin "5") (pinfunction "PD0-OSC_IN_5") (pintype "input"))
    )
    (net (code "172") (name "unconnected-(U2-PD1-OSC_OUT-Pad6)") (class "Default")
      (node (ref "U2") (pin "6") (pinfunction "PD1-OSC_OUT_6") (pintype "output"))
    )
    (net (code "173") (name "unconnected-(X0-PA13{slash}SPI1_CS-Pad24)") (class "Default")
      (node (ref "X0") (pin "24") (pinfunction "PA13/SPI1_CS_24") (pintype "bidirectional"))
    )
    (net (code "174") (name "unconnected-(X0-PA14{slash}SPI1_CLK-Pad23)") (class "Default")
      (node (ref "X0") (pin "23") (pinfunction "PA14/SPI1_CLK_23") (pintype "bidirectional"))
    )
    (net (code "175") (name "unconnected-(X0-PA15{slash}SPI1_MOSI-Pad19)") (class "Default")
      (node (ref "X0") (pin "19") (pinfunction "PA15/SPI1_MOSI_19") (pintype "bidirectional"))
    )
    (net (code "176") (name "unconnected-(X0-PA16{slash}SPI1_MISO-Pad21)") (class "Default")
      (node (ref "X0") (pin "21") (pinfunction "PA16/SPI1_MISO_21") (pintype "bidirectional"))
    )
    (net (code "177") (name "unconnected-(X0-PA18{slash}TWI1_SCL-Pad18)") (class "Default")
      (node (ref "X0") (pin "18") (pinfunction "PA18/TWI1_SCL_18") (pintype "bidirectional"))
    )
    (net (code "178") (name "unconnected-(X0-PA19{slash}TWI1_SDA-Pad16)") (class "Default")
      (node (ref "X0") (pin "16") (pinfunction "PA19/TWI1_SDA_16") (pintype "bidirectional"))
    )
    (net (code "179") (name "unconnected-(X0-SIM_DET{slash}PA_EINT10{slash}PA10-Pad26)") (class "Default")
      (node (ref "X0") (pin "26") (pinfunction "SIM_DET/PA_EINT10/PA10_26") (pintype "bidirectional"))
    )
    (net (code "180") (name "unconnected-(X0-UART2_CTS{slash}PA03-Pad15)") (class "Default")
      (node (ref "X0") (pin "15") (pinfunction "UART2_CTS/PA03_15") (pintype "bidirectional"))
    )
    (net (code "181") (name "unconnected-(X0-UART2_RTS{slash}PA02-Pad22)") (class "Default")
      (node (ref "X0") (pin "22") (pinfunction "UART2_RTS/PA02_22") (pintype "bidirectional"))
    )
  )
)
